# mdu29.net
KiCad netlist of a schematic drawn in EAGLE
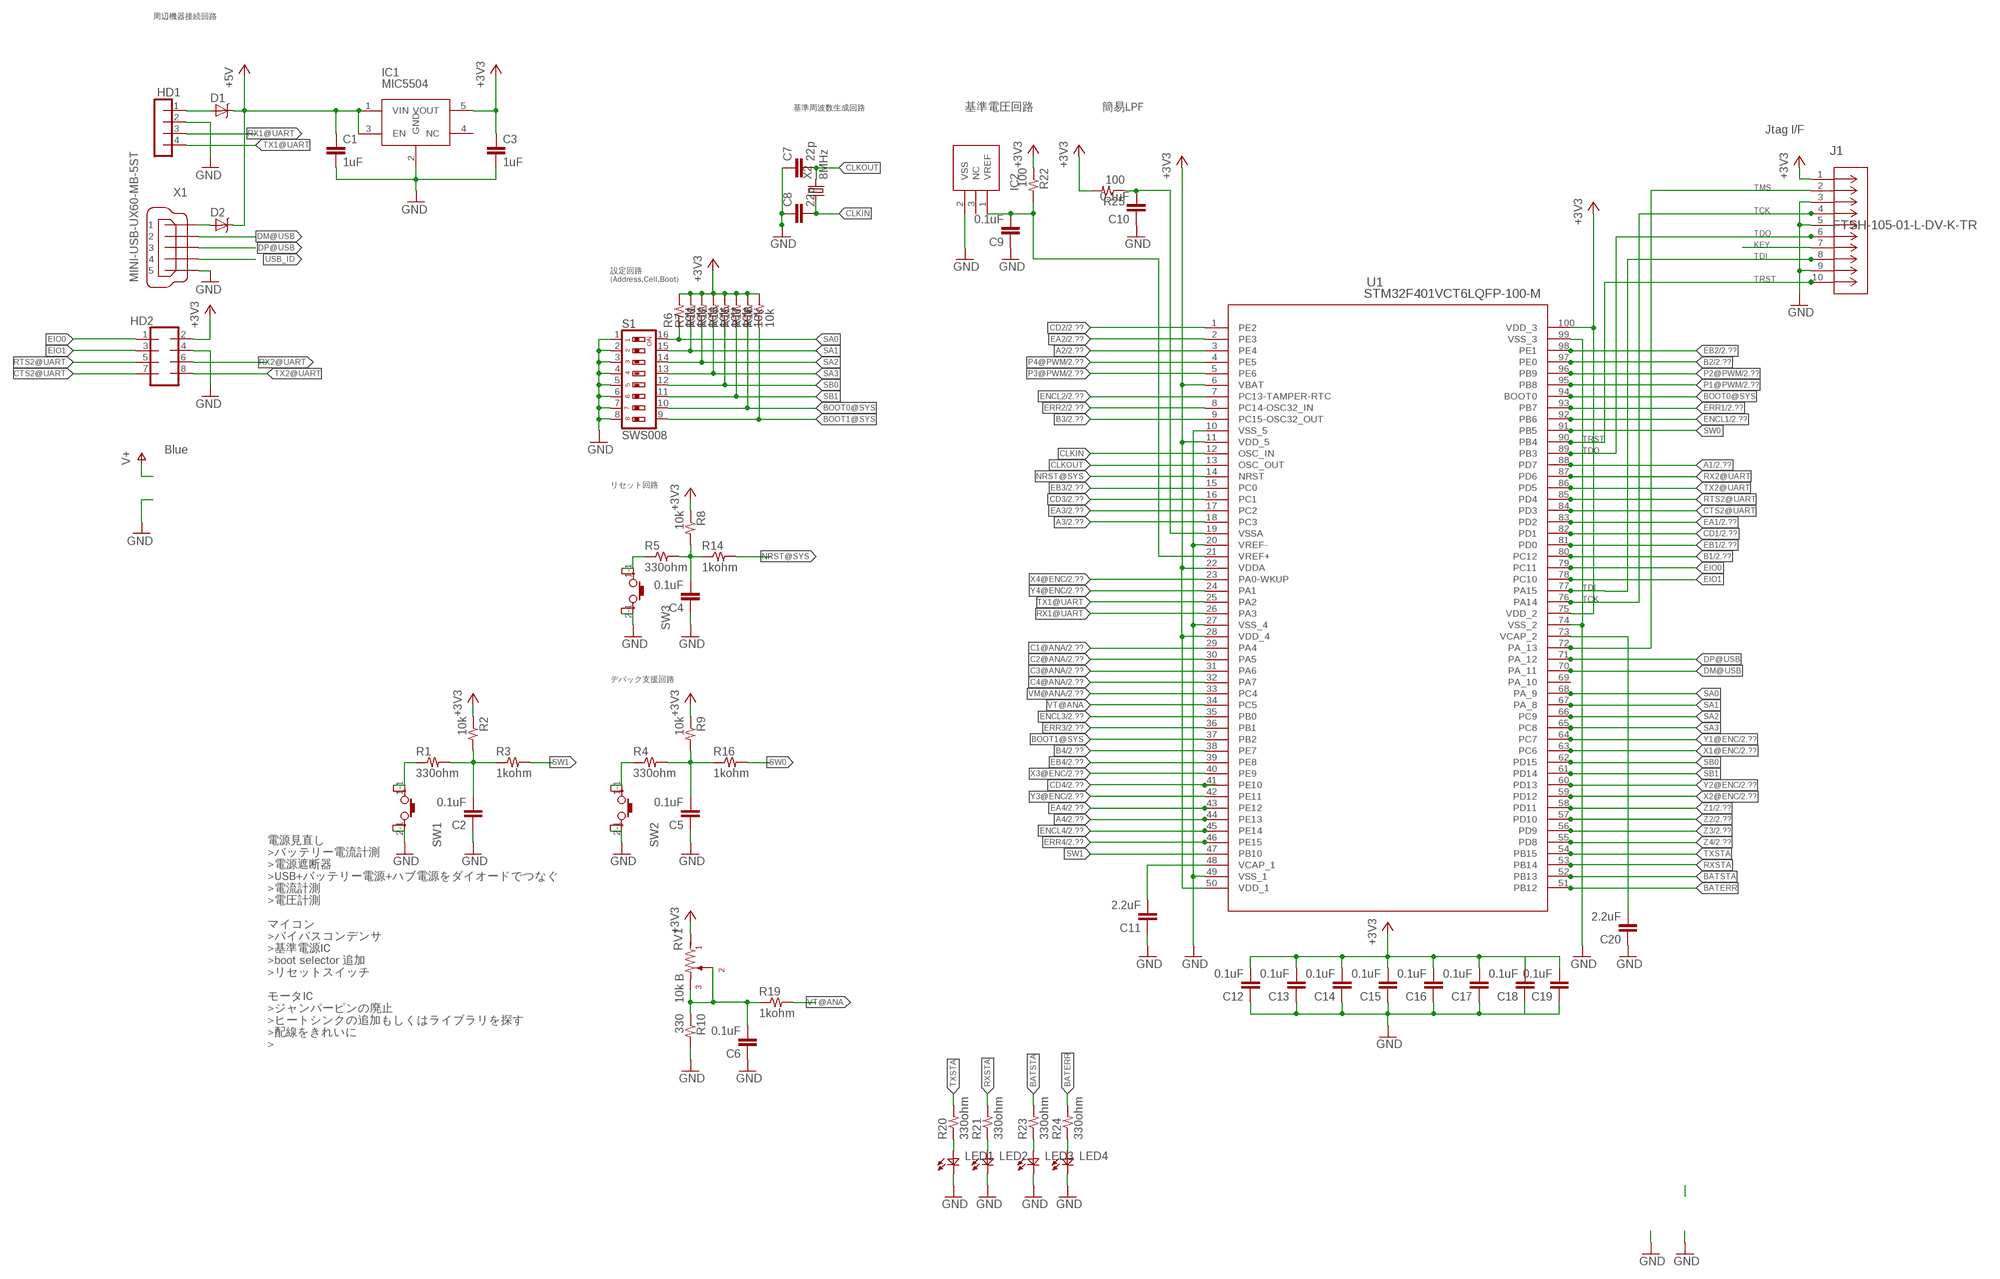
[diagram p0: schematic, sheet 1]
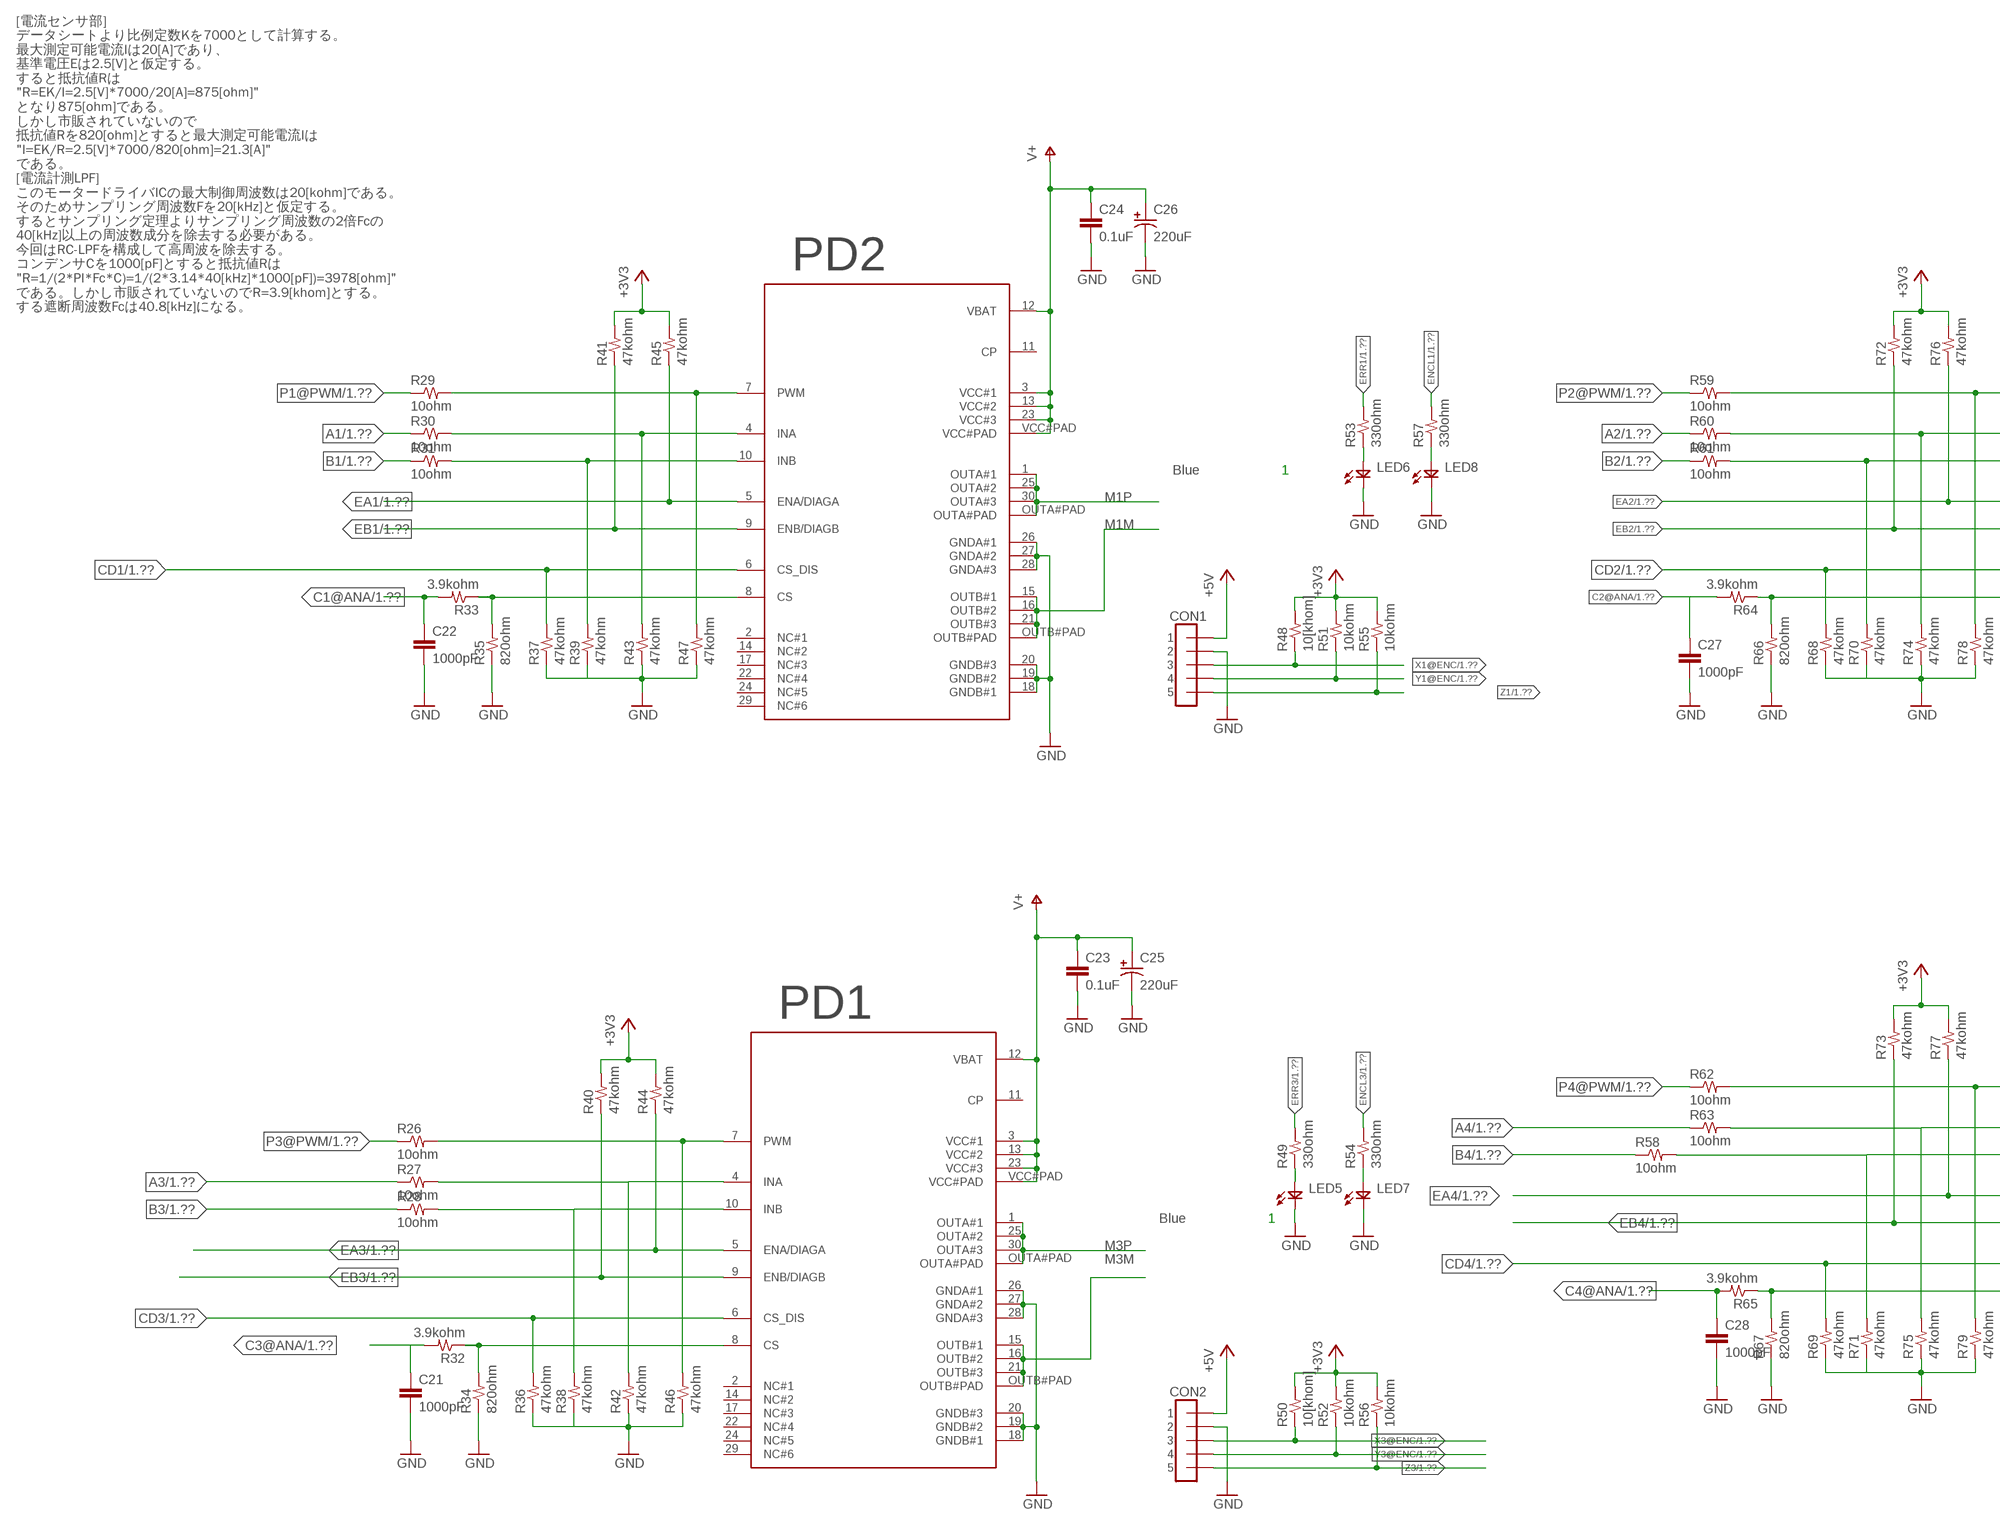
[diagram p1: schematic, sheet 2, part 1 of 2]
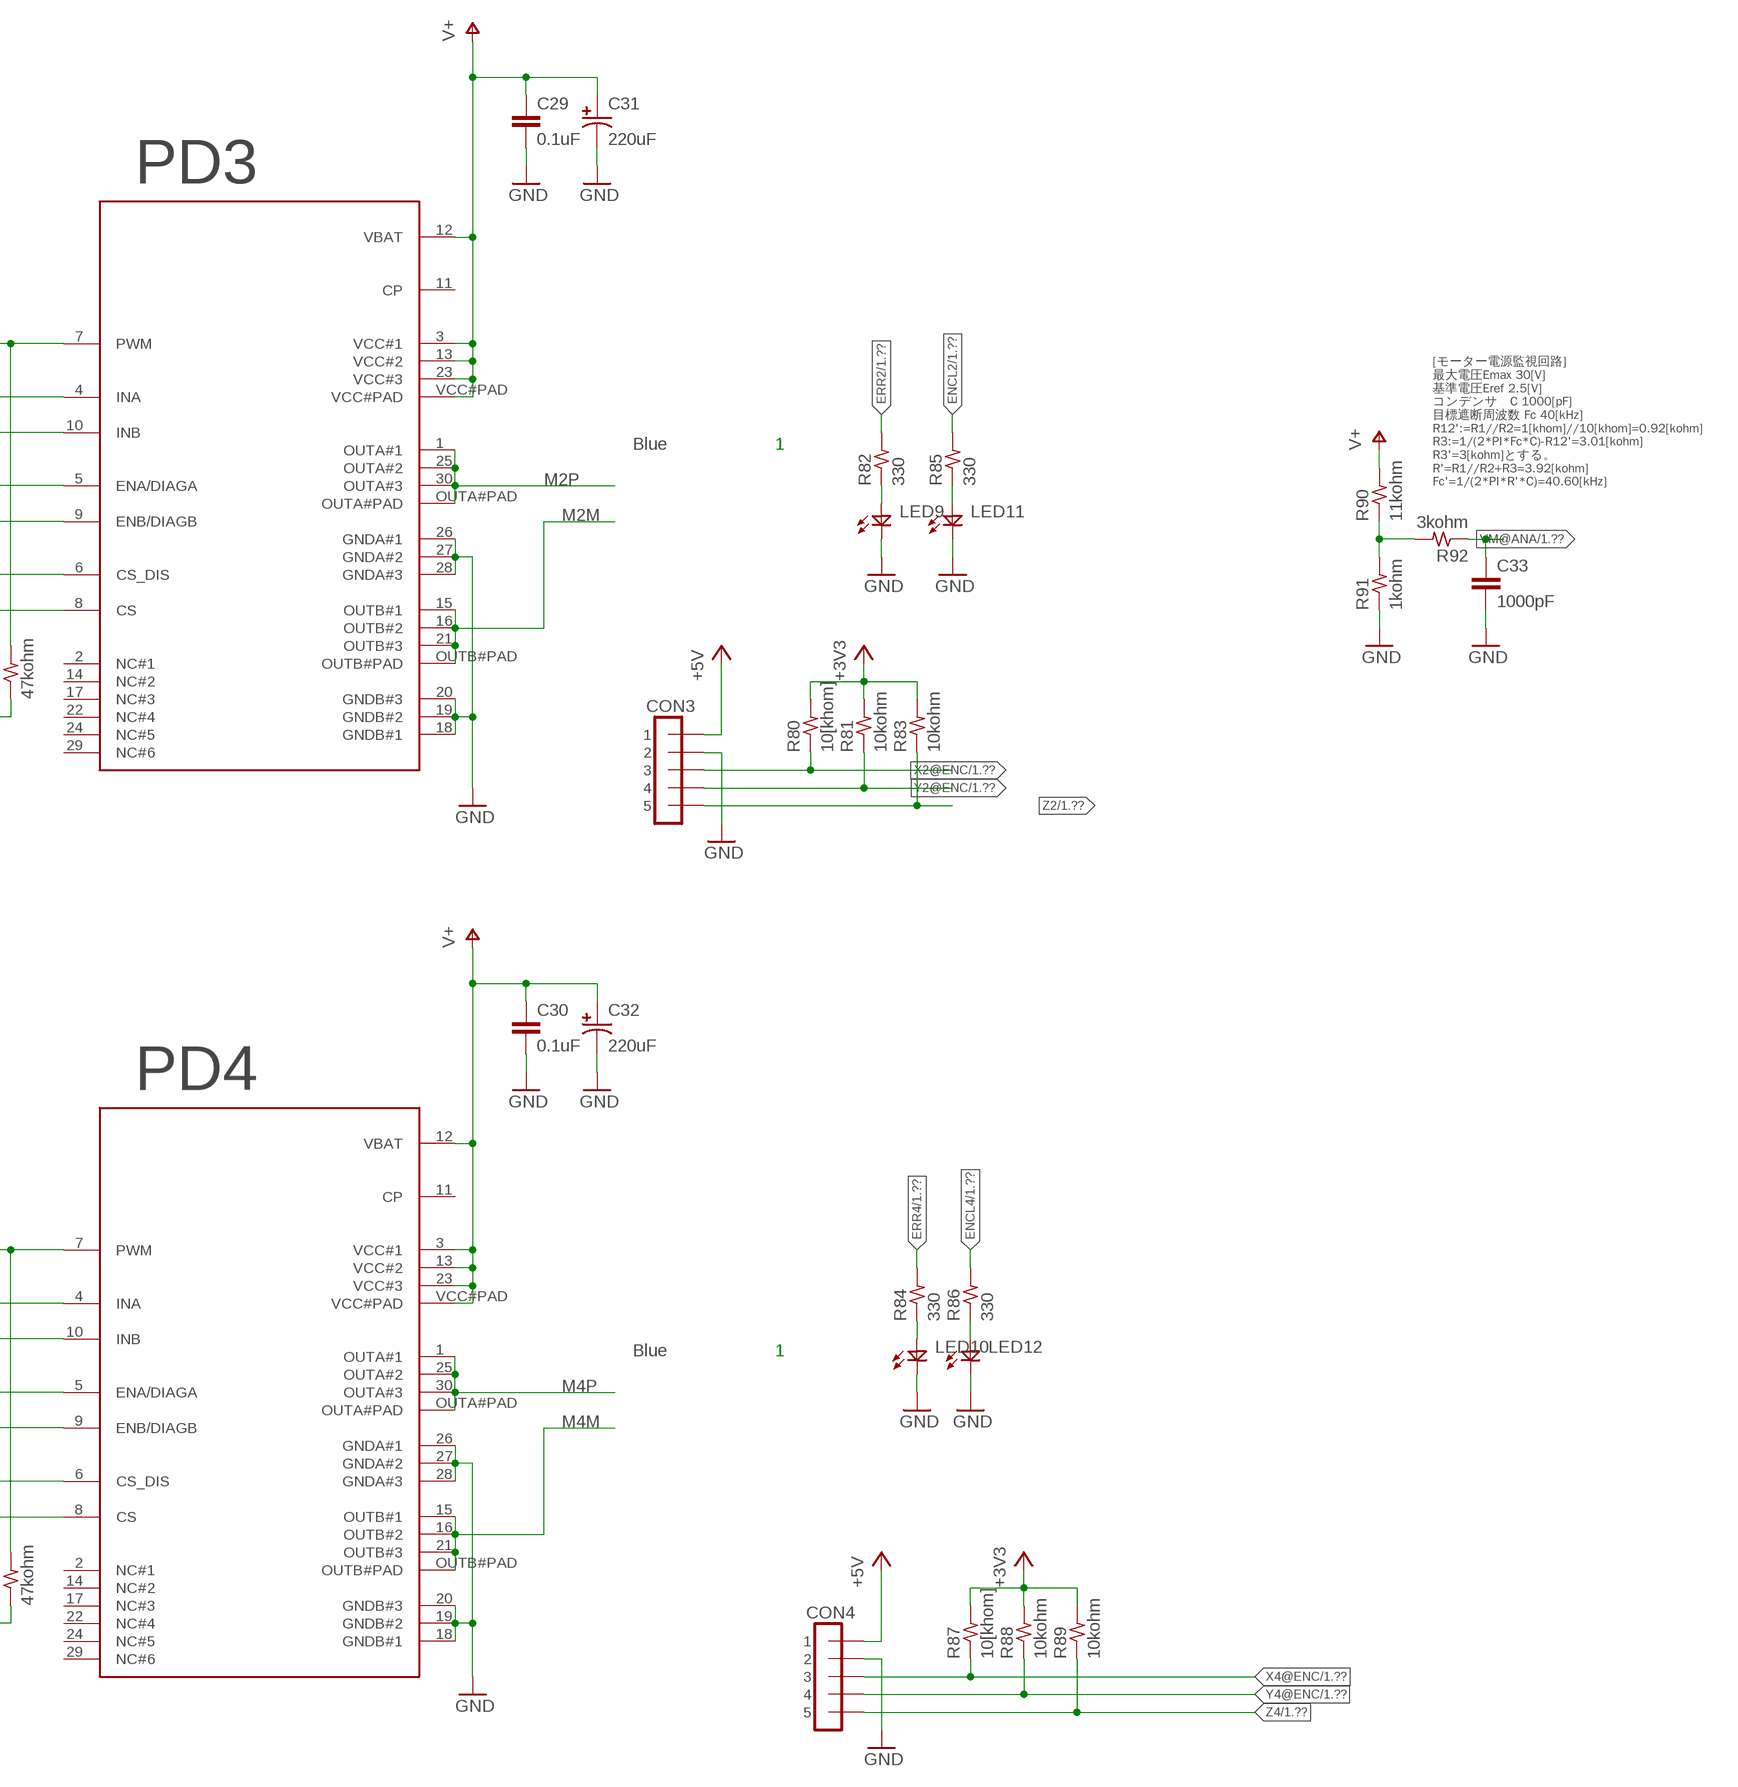
[diagram p2: schematic, sheet 2, part 2 of 2]

(export (version "E")
  (design (tool "Eeschema 10.0.6"))
  (components
    (comp (ref "C21")
      (value "1000pF")
      (footprint "eagle-import:1608")
      (libsource (lib "eagle-import") (part "C1608"))
    )
    (comp (ref "C22")
      (value "1000pF")
      (footprint "eagle-import:1608")
      (libsource (lib "eagle-import") (part "C1608"))
    )
    (comp (ref "C23")
      (value "0.1uF")
      (footprint "eagle-import:1608")
      (libsource (lib "eagle-import") (part "C1608"))
    )
    (comp (ref "C24")
      (value "0.1uF")
      (footprint "eagle-import:1608")
      (libsource (lib "eagle-import") (part "C1608"))
    )
    (comp (ref "C25")
      (value "220uF")
      (footprint "eagle-import:ES-12.5")
      (libsource (lib "eagle-import") (part "CPOLS-12.5"))
    )
    (comp (ref "C26")
      (value "220uF")
      (footprint "eagle-import:ES-12.5")
      (libsource (lib "eagle-import") (part "CPOLS-12.5"))
    )
    (comp (ref "C27")
      (value "1000pF")
      (footprint "eagle-import:1608")
      (libsource (lib "eagle-import") (part "C1608"))
    )
    (comp (ref "C28")
      (value "1000pF")
      (footprint "eagle-import:1608")
      (libsource (lib "eagle-import") (part "C1608"))
    )
    (comp (ref "C29")
      (value "0.1uF")
      (footprint "eagle-import:1608")
      (libsource (lib "eagle-import") (part "C1608"))
    )
    (comp (ref "C30")
      (value "0.1uF")
      (footprint "eagle-import:1608")
      (libsource (lib "eagle-import") (part "C1608"))
    )
    (comp (ref "C31")
      (value "220uF")
      (footprint "eagle-import:ES-12.5")
      (libsource (lib "eagle-import") (part "CPOLS-12.5"))
    )
    (comp (ref "C32")
      (value "220uF")
      (footprint "eagle-import:ES-12.5")
      (libsource (lib "eagle-import") (part "CPOLS-12.5"))
    )
    (comp (ref "C33")
      (value "1000pF")
      (footprint "eagle-import:1608")
      (libsource (lib "eagle-import") (part "C1608"))
    )
    (comp (ref "CON1")
      (value "CON-5")
      (footprint "eagle-import:5-L")
      (libsource (lib "eagle-import") (part "CON-5"))
    )
    (comp (ref "CON2")
      (value "CON-5")
      (footprint "eagle-import:5-L")
      (libsource (lib "eagle-import") (part "CON-5"))
    )
    (comp (ref "CON3")
      (value "CON-5")
      (footprint "eagle-import:5-L")
      (libsource (lib "eagle-import") (part "CON-5"))
    )
    (comp (ref "CON4")
      (value "CON-5")
      (footprint "eagle-import:5-L")
      (libsource (lib "eagle-import") (part "CON-5"))
    )
    (comp (ref "LED5")
      (value "LED1608")
      (footprint "eagle-import:1608")
      (libsource (lib "eagle-import") (part "LED1608"))
    )
    (comp (ref "LED6")
      (value "LED1608")
      (footprint "eagle-import:1608")
      (libsource (lib "eagle-import") (part "LED1608"))
    )
    (comp (ref "LED7")
      (value "LED1608")
      (footprint "eagle-import:1608")
      (libsource (lib "eagle-import") (part "LED1608"))
    )
    (comp (ref "LED8")
      (value "LED1608")
      (footprint "eagle-import:1608")
      (libsource (lib "eagle-import") (part "LED1608"))
    )
    (comp (ref "LED9")
      (value "LED1608")
      (footprint "eagle-import:1608")
      (libsource (lib "eagle-import") (part "LED1608"))
    )
    (comp (ref "LED10")
      (value "LED1608")
      (footprint "eagle-import:1608")
      (libsource (lib "eagle-import") (part "LED1608"))
    )
    (comp (ref "LED11")
      (value "LED1608")
      (footprint "eagle-import:1608")
      (libsource (lib "eagle-import") (part "LED1608"))
    )
    (comp (ref "LED12")
      (value "LED1608")
      (footprint "eagle-import:1608")
      (libsource (lib "eagle-import") (part "LED1608"))
    )
    (comp (ref "PD1")
      (value "VNH5019")
      (footprint "eagle-import:VNH5019")
      (libsource (lib "eagle-import") (part "VNH5019"))
    )
    (comp (ref "PD2")
      (value "VNH5019")
      (footprint "eagle-import:VNH5019")
      (libsource (lib "eagle-import") (part "VNH5019"))
    )
    (comp (ref "PD3")
      (value "VNH5019")
      (footprint "eagle-import:VNH5019")
      (libsource (lib "eagle-import") (part "VNH5019"))
    )
    (comp (ref "PD4")
      (value "VNH5019")
      (footprint "eagle-import:VNH5019")
      (libsource (lib "eagle-import") (part "VNH5019"))
    )
    (comp (ref "R26")
      (value "10ohm")
      (footprint "eagle-import:1608")
      (libsource (lib "eagle-import") (part "R1608"))
    )
    (comp (ref "R27")
      (value "10ohm")
      (footprint "eagle-import:1608")
      (libsource (lib "eagle-import") (part "R1608"))
    )
    (comp (ref "R28")
      (value "10ohm")
      (footprint "eagle-import:1608")
      (libsource (lib "eagle-import") (part "R1608"))
    )
    (comp (ref "R29")
      (value "10ohm")
      (footprint "eagle-import:1608")
      (libsource (lib "eagle-import") (part "R1608"))
    )
    (comp (ref "R30")
      (value "10ohm")
      (footprint "eagle-import:1608")
      (libsource (lib "eagle-import") (part "R1608"))
    )
    (comp (ref "R31")
      (value "10ohm")
      (footprint "eagle-import:1608")
      (libsource (lib "eagle-import") (part "R1608"))
    )
    (comp (ref "R32")
      (value "3.9kohm")
      (footprint "eagle-import:1608")
      (libsource (lib "eagle-import") (part "R1608"))
    )
    (comp (ref "R33")
      (value "3.9kohm")
      (footprint "eagle-import:1608")
      (libsource (lib "eagle-import") (part "R1608"))
    )
    (comp (ref "R34")
      (value "820ohm")
      (footprint "eagle-import:1608")
      (libsource (lib "eagle-import") (part "R1608"))
    )
    (comp (ref "R35")
      (value "820ohm")
      (footprint "eagle-import:1608")
      (libsource (lib "eagle-import") (part "R1608"))
    )
    (comp (ref "R36")
      (value "47kohm")
      (footprint "eagle-import:1608")
      (libsource (lib "eagle-import") (part "R1608"))
    )
    (comp (ref "R37")
      (value "47kohm")
      (footprint "eagle-import:1608")
      (libsource (lib "eagle-import") (part "R1608"))
    )
    (comp (ref "R38")
      (value "47kohm")
      (footprint "eagle-import:1608")
      (libsource (lib "eagle-import") (part "R1608"))
    )
    (comp (ref "R39")
      (value "47kohm")
      (footprint "eagle-import:1608")
      (libsource (lib "eagle-import") (part "R1608"))
    )
    (comp (ref "R40")
      (value "47kohm")
      (footprint "eagle-import:1608")
      (libsource (lib "eagle-import") (part "R1608"))
    )
    (comp (ref "R41")
      (value "47kohm")
      (footprint "eagle-import:1608")
      (libsource (lib "eagle-import") (part "R1608"))
    )
    (comp (ref "R42")
      (value "47kohm")
      (footprint "eagle-import:1608")
      (libsource (lib "eagle-import") (part "R1608"))
    )
    (comp (ref "R43")
      (value "47kohm")
      (footprint "eagle-import:1608")
      (libsource (lib "eagle-import") (part "R1608"))
    )
    (comp (ref "R44")
      (value "47kohm")
      (footprint "eagle-import:1608")
      (libsource (lib "eagle-import") (part "R1608"))
    )
    (comp (ref "R45")
      (value "47kohm")
      (footprint "eagle-import:1608")
      (libsource (lib "eagle-import") (part "R1608"))
    )
    (comp (ref "R46")
      (value "47kohm")
      (footprint "eagle-import:1608")
      (libsource (lib "eagle-import") (part "R1608"))
    )
    (comp (ref "R47")
      (value "47kohm")
      (footprint "eagle-import:1608")
      (libsource (lib "eagle-import") (part "R1608"))
    )
    (comp (ref "R48")
      (value "10[khom]")
      (footprint "eagle-import:1608")
      (libsource (lib "eagle-import") (part "R1608"))
    )
    (comp (ref "R49")
      (value "330ohm")
      (footprint "eagle-import:1608")
      (libsource (lib "eagle-import") (part "R1608"))
    )
    (comp (ref "R50")
      (value "10[khom]")
      (footprint "eagle-import:1608")
      (libsource (lib "eagle-import") (part "R1608"))
    )
    (comp (ref "R51")
      (value "10kohm")
      (footprint "eagle-import:1608")
      (libsource (lib "eagle-import") (part "R1608"))
    )
    (comp (ref "R52")
      (value "10kohm")
      (footprint "eagle-import:1608")
      (libsource (lib "eagle-import") (part "R1608"))
    )
    (comp (ref "R53")
      (value "330ohm")
      (footprint "eagle-import:1608")
      (libsource (lib "eagle-import") (part "R1608"))
    )
    (comp (ref "R54")
      (value "330ohm")
      (footprint "eagle-import:1608")
      (libsource (lib "eagle-import") (part "R1608"))
    )
    (comp (ref "R55")
      (value "10kohm")
      (footprint "eagle-import:1608")
      (libsource (lib "eagle-import") (part "R1608"))
    )
    (comp (ref "R56")
      (value "10kohm")
      (footprint "eagle-import:1608")
      (libsource (lib "eagle-import") (part "R1608"))
    )
    (comp (ref "R57")
      (value "330ohm")
      (footprint "eagle-import:1608")
      (libsource (lib "eagle-import") (part "R1608"))
    )
    (comp (ref "R58")
      (value "10ohm")
      (footprint "eagle-import:1608")
      (libsource (lib "eagle-import") (part "R1608"))
    )
    (comp (ref "R59")
      (value "10ohm")
      (footprint "eagle-import:1608")
      (libsource (lib "eagle-import") (part "R1608"))
    )
    (comp (ref "R60")
      (value "10ohm")
      (footprint "eagle-import:1608")
      (libsource (lib "eagle-import") (part "R1608"))
    )
    (comp (ref "R61")
      (value "10ohm")
      (footprint "eagle-import:1608")
      (libsource (lib "eagle-import") (part "R1608"))
    )
    (comp (ref "R62")
      (value "10ohm")
      (footprint "eagle-import:1608")
      (libsource (lib "eagle-import") (part "R1608"))
    )
    (comp (ref "R63")
      (value "10ohm")
      (footprint "eagle-import:1608")
      (libsource (lib "eagle-import") (part "R1608"))
    )
    (comp (ref "R64")
      (value "3.9kohm")
      (footprint "eagle-import:1608")
      (libsource (lib "eagle-import") (part "R1608"))
    )
    (comp (ref "R65")
      (value "3.9kohm")
      (footprint "eagle-import:1608")
      (libsource (lib "eagle-import") (part "R1608"))
    )
    (comp (ref "R66")
      (value "820ohm")
      (footprint "eagle-import:1608")
      (libsource (lib "eagle-import") (part "R1608"))
    )
    (comp (ref "R67")
      (value "820ohm")
      (footprint "eagle-import:1608")
      (libsource (lib "eagle-import") (part "R1608"))
    )
    (comp (ref "R68")
      (value "47kohm")
      (footprint "eagle-import:1608")
      (libsource (lib "eagle-import") (part "R1608"))
    )
    (comp (ref "R69")
      (value "47kohm")
      (footprint "eagle-import:1608")
      (libsource (lib "eagle-import") (part "R1608"))
    )
    (comp (ref "R70")
      (value "47kohm")
      (footprint "eagle-import:1608")
      (libsource (lib "eagle-import") (part "R1608"))
    )
    (comp (ref "R71")
      (value "47kohm")
      (footprint "eagle-import:1608")
      (libsource (lib "eagle-import") (part "R1608"))
    )
    (comp (ref "R72")
      (value "47kohm")
      (footprint "eagle-import:1608")
      (libsource (lib "eagle-import") (part "R1608"))
    )
    (comp (ref "R73")
      (value "47kohm")
      (footprint "eagle-import:1608")
      (libsource (lib "eagle-import") (part "R1608"))
    )
    (comp (ref "R74")
      (value "47kohm")
      (footprint "eagle-import:1608")
      (libsource (lib "eagle-import") (part "R1608"))
    )
    (comp (ref "R75")
      (value "47kohm")
      (footprint "eagle-import:1608")
      (libsource (lib "eagle-import") (part "R1608"))
    )
    (comp (ref "R76")
      (value "47kohm")
      (footprint "eagle-import:1608")
      (libsource (lib "eagle-import") (part "R1608"))
    )
    (comp (ref "R77")
      (value "47kohm")
      (footprint "eagle-import:1608")
      (libsource (lib "eagle-import") (part "R1608"))
    )
    (comp (ref "R78")
      (value "47kohm")
      (footprint "eagle-import:1608")
      (libsource (lib "eagle-import") (part "R1608"))
    )
    (comp (ref "R79")
      (value "47kohm")
      (footprint "eagle-import:1608")
      (libsource (lib "eagle-import") (part "R1608"))
    )
    (comp (ref "R80")
      (value "10[khom]")
      (footprint "eagle-import:1608")
      (libsource (lib "eagle-import") (part "R1608"))
    )
    (comp (ref "R81")
      (value "10kohm")
      (footprint "eagle-import:1608")
      (libsource (lib "eagle-import") (part "R1608"))
    )
    (comp (ref "R82")
      (value "330")
      (footprint "eagle-import:1608")
      (libsource (lib "eagle-import") (part "R1608"))
    )
    (comp (ref "R83")
      (value "10kohm")
      (footprint "eagle-import:1608")
      (libsource (lib "eagle-import") (part "R1608"))
    )
    (comp (ref "R84")
      (value "330")
      (footprint "eagle-import:1608")
      (libsource (lib "eagle-import") (part "R1608"))
    )
    (comp (ref "R85")
      (value "330")
      (footprint "eagle-import:1608")
      (libsource (lib "eagle-import") (part "R1608"))
    )
    (comp (ref "R86")
      (value "330")
      (footprint "eagle-import:1608")
      (libsource (lib "eagle-import") (part "R1608"))
    )
    (comp (ref "R87")
      (value "10[khom]")
      (footprint "eagle-import:1608")
      (libsource (lib "eagle-import") (part "R1608"))
    )
    (comp (ref "R88")
      (value "10kohm")
      (footprint "eagle-import:1608")
      (libsource (lib "eagle-import") (part "R1608"))
    )
    (comp (ref "R89")
      (value "10kohm")
      (footprint "eagle-import:1608")
      (libsource (lib "eagle-import") (part "R1608"))
    )
    (comp (ref "R90")
      (value "11kohm")
      (footprint "eagle-import:1608")
      (libsource (lib "eagle-import") (part "R1608"))
    )
    (comp (ref "R91")
      (value "1kohm")
      (footprint "eagle-import:1608")
      (libsource (lib "eagle-import") (part "R1608"))
    )
    (comp (ref "R92")
      (value "3kohm")
      (footprint "eagle-import:1608")
      (libsource (lib "eagle-import") (part "R1608"))
    )
    (comp (ref "C1")
      (value "1uF")
      (footprint "eagle-import:1608")
      (libsource (lib "eagle-import") (part "C1608"))
    )
    (comp (ref "C2")
      (value "0.1uF")
      (footprint "eagle-import:1608")
      (libsource (lib "eagle-import") (part "C1608"))
    )
    (comp (ref "C3")
      (value "1uF")
      (footprint "eagle-import:1608")
      (libsource (lib "eagle-import") (part "C1608"))
    )
    (comp (ref "C4")
      (value "0.1uF")
      (footprint "eagle-import:1608")
      (libsource (lib "eagle-import") (part "C1608"))
    )
    (comp (ref "C5")
      (value "0.1uF")
      (footprint "eagle-import:1608")
      (libsource (lib "eagle-import") (part "C1608"))
    )
    (comp (ref "C6")
      (value "0.1uF")
      (footprint "eagle-import:1608")
      (libsource (lib "eagle-import") (part "C1608"))
    )
    (comp (ref "C7")
      (value "22p")
      (footprint "eagle-import:1608")
      (libsource (lib "eagle-import") (part "C1608"))
    )
    (comp (ref "C8")
      (value "22p")
      (footprint "eagle-import:1608")
      (libsource (lib "eagle-import") (part "C1608"))
    )
    (comp (ref "C9")
      (value "0.1uF")
      (footprint "eagle-import:1608")
      (libsource (lib "eagle-import") (part "C1608"))
    )
    (comp (ref "C10")
      (value "0.1uF")
      (footprint "eagle-import:1608")
      (libsource (lib "eagle-import") (part "C1608"))
    )
    (comp (ref "C11")
      (value "2.2uF")
      (footprint "eagle-import:1608")
      (libsource (lib "eagle-import") (part "C1608"))
    )
    (comp (ref "C12")
      (value "0.1uF")
      (footprint "eagle-import:1608")
      (libsource (lib "eagle-import") (part "C1608"))
    )
    (comp (ref "C13")
      (value "0.1uF")
      (footprint "eagle-import:1608")
      (libsource (lib "eagle-import") (part "C1608"))
    )
    (comp (ref "C14")
      (value "0.1uF")
      (footprint "eagle-import:1608")
      (libsource (lib "eagle-import") (part "C1608"))
    )
    (comp (ref "C15")
      (value "0.1uF")
      (footprint "eagle-import:1608")
      (libsource (lib "eagle-import") (part "C1608"))
    )
    (comp (ref "C16")
      (value "0.1uF")
      (footprint "eagle-import:1608")
      (libsource (lib "eagle-import") (part "C1608"))
    )
    (comp (ref "C17")
      (value "0.1uF")
      (footprint "eagle-import:1608")
      (libsource (lib "eagle-import") (part "C1608"))
    )
    (comp (ref "C18")
      (value "0.1uF")
      (footprint "eagle-import:1608")
      (libsource (lib "eagle-import") (part "C1608"))
    )
    (comp (ref "C19")
      (value "0.1uF")
      (footprint "eagle-import:1608")
      (libsource (lib "eagle-import") (part "C1608"))
    )
    (comp (ref "C20")
      (value "2.2uF")
      (footprint "eagle-import:1608")
      (libsource (lib "eagle-import") (part "C1608"))
    )
    (comp (ref "D1")
      (value "ZENER-SOD523")
      (footprint "eagle-import:SOD523")
      (libsource (lib "eagle-import") (part "ZENER-SOD523"))
    )
    (comp (ref "D2")
      (value "ZENER-SOD523")
      (footprint "eagle-import:SOD523")
      (libsource (lib "eagle-import") (part "ZENER-SOD523"))
    )
    (comp (ref "HD1")
      (value "1X4L")
      (footprint "eagle-import:1X4-L")
      (libsource (lib "eagle-import") (part "1X4L"))
    )
    (comp (ref "HD2")
      (value "2X4I")
      (footprint "eagle-import:2X4-I")
      (libsource (lib "eagle-import") (part "2X4I"))
    )
    (comp (ref "IC1")
      (value "MIC5504")
      (footprint "eagle-import:SOT95P270X145-5N")
      (libsource (lib "eagle-import") (part "MIC5504"))
    )
    (comp (ref "IC2")
      (value "LM4040")
      (footprint "eagle-import:SOT23")
      (libsource (lib "eagle-import") (part "LM4040"))
    )
    (comp (ref "J1")
      (value "FTSH-105-01-L-DV-K-TR")
      (footprint "eagle-import:CON10_2X5_DUK_FTSH")
      (fields
        (field (name "DIGIKEYPARTNUMBER") "FTSH-105-01-L-DV-K-TR-ND")
        (field (name "COPYRIGHT") "Copyright (C) 2015 Accelerated Designs. All rights reserved")
      )
      (libsource (lib "eagle-import") (part "FTSH-105-01-L-DV-K-TR"))
    )
    (comp (ref "LED1")
      (value "LED1608")
      (footprint "eagle-import:1608")
      (libsource (lib "eagle-import") (part "LED1608"))
    )
    (comp (ref "LED2")
      (value "LED1608")
      (footprint "eagle-import:1608")
      (libsource (lib "eagle-import") (part "LED1608"))
    )
    (comp (ref "LED3")
      (value "LED1608")
      (footprint "eagle-import:1608")
      (libsource (lib "eagle-import") (part "LED1608"))
    )
    (comp (ref "LED4")
      (value "LED1608")
      (footprint "eagle-import:1608")
      (libsource (lib "eagle-import") (part "LED1608"))
    )
    (comp (ref "R1")
      (value "330ohm")
      (footprint "eagle-import:1608")
      (libsource (lib "eagle-import") (part "R1608"))
    )
    (comp (ref "R2")
      (value "10k")
      (footprint "eagle-import:1608")
      (libsource (lib "eagle-import") (part "R1608"))
    )
    (comp (ref "R3")
      (value "1kohm")
      (footprint "eagle-import:1608")
      (libsource (lib "eagle-import") (part "R1608"))
    )
    (comp (ref "R4")
      (value "330ohm")
      (footprint "eagle-import:1608")
      (libsource (lib "eagle-import") (part "R1608"))
    )
    (comp (ref "R5")
      (value "330ohm")
      (footprint "eagle-import:1608")
      (libsource (lib "eagle-import") (part "R1608"))
    )
    (comp (ref "R6")
      (value "10k")
      (footprint "eagle-import:1608")
      (libsource (lib "eagle-import") (part "R1608"))
    )
    (comp (ref "R7")
      (value "10k")
      (footprint "eagle-import:1608")
      (libsource (lib "eagle-import") (part "R1608"))
    )
    (comp (ref "R8")
      (value "10k")
      (footprint "eagle-import:1608")
      (libsource (lib "eagle-import") (part "R1608"))
    )
    (comp (ref "R9")
      (value "10k")
      (footprint "eagle-import:1608")
      (libsource (lib "eagle-import") (part "R1608"))
    )
    (comp (ref "R10")
      (value "330")
      (footprint "eagle-import:1608")
      (libsource (lib "eagle-import") (part "R1608"))
    )
    (comp (ref "R11")
      (value "10k")
      (footprint "eagle-import:1608")
      (libsource (lib "eagle-import") (part "R1608"))
    )
    (comp (ref "R12")
      (value "10k")
      (footprint "eagle-import:1608")
      (libsource (lib "eagle-import") (part "R1608"))
    )
    (comp (ref "R13")
      (value "10k")
      (footprint "eagle-import:1608")
      (libsource (lib "eagle-import") (part "R1608"))
    )
    (comp (ref "R14")
      (value "1kohm")
      (footprint "eagle-import:1608")
      (libsource (lib "eagle-import") (part "R1608"))
    )
    (comp (ref "R15")
      (value "10k")
      (footprint "eagle-import:1608")
      (libsource (lib "eagle-import") (part "R1608"))
    )
    (comp (ref "R16")
      (value "1kohm")
      (footprint "eagle-import:1608")
      (libsource (lib "eagle-import") (part "R1608"))
    )
    (comp (ref "R17")
      (value "10k")
      (footprint "eagle-import:1608")
      (libsource (lib "eagle-import") (part "R1608"))
    )
    (comp (ref "R18")
      (value "10k")
      (footprint "eagle-import:1608")
      (libsource (lib "eagle-import") (part "R1608"))
    )
    (comp (ref "R19")
      (value "1kohm")
      (footprint "eagle-import:1608")
      (libsource (lib "eagle-import") (part "R1608"))
    )
    (comp (ref "R20")
      (value "330ohm")
      (footprint "eagle-import:1608")
      (libsource (lib "eagle-import") (part "R1608"))
    )
    (comp (ref "R21")
      (value "330ohm")
      (footprint "eagle-import:1608")
      (libsource (lib "eagle-import") (part "R1608"))
    )
    (comp (ref "R22")
      (value "100")
      (footprint "eagle-import:1608")
      (libsource (lib "eagle-import") (part "R1608"))
    )
    (comp (ref "R23")
      (value "330ohm")
      (footprint "eagle-import:1608")
      (libsource (lib "eagle-import") (part "R1608"))
    )
    (comp (ref "R24")
      (value "330ohm")
      (footprint "eagle-import:1608")
      (libsource (lib "eagle-import") (part "R1608"))
    )
    (comp (ref "R25")
      (value "100")
      (footprint "eagle-import:1608")
      (libsource (lib "eagle-import") (part "R1608"))
    )
    (comp (ref "RV1")
      (value "10k B")
      (footprint "eagle-import:RV")
      (libsource (lib "eagle-import") (part "RV"))
    )
    (comp (ref "S1")
      (value "SWS008")
      (footprint "eagle-import:SMS-008")
      (libsource (lib "eagle-import") (part "SWS008"))
    )
    (comp (ref "SW1")
      (value "TACTSW1")
      (footprint "eagle-import:PUSHSW-1")
      (libsource (lib "eagle-import") (part "TACTSW1"))
    )
    (comp (ref "SW2")
      (value "TACTSW1")
      (footprint "eagle-import:PUSHSW-1")
      (libsource (lib "eagle-import") (part "TACTSW1"))
    )
    (comp (ref "SW3")
      (value "TACTSW1")
      (footprint "eagle-import:PUSHSW-1")
      (libsource (lib "eagle-import") (part "TACTSW1"))
    )
    (comp (ref "U1")
      (value "STM32F401VCT6LQFP-100-M")
      (footprint "eagle-import:LQFP-100-M")
      (fields (field (name "MANUFACTURER_PART_NUMBER") "STM32F401VCT6"))
      (libsource (lib "eagle-import") (part "STM32F401VCT6LQFP-100-M"))
    )
    (comp (ref "X1")
      (value "MINI-USB-UX60-MB-5ST")
      (footprint "eagle-import:UX60-MB-5ST")
      (libsource (lib "eagle-import") (part "MINI-USB-UX60-MB-5ST"))
    )
    (comp (ref "X2")
      (value "8MHz")
      (footprint "eagle-import:XTAL")
      (libsource (lib "eagle-import") (part "CRYSTALHC49S"))
    )
  )
  (nets
    (net (code "1") (name "+3V3") (class "Default")
      (node (ref "C12") (pin "2") (pinfunction "2_2") (pintype "passive"))
      (node (ref "C13") (pin "2") (pinfunction "2_2") (pintype "passive"))
      (node (ref "C14") (pin "2") (pinfunction "2_2") (pintype "passive"))
      (node (ref "C15") (pin "2") (pinfunction "2_2") (pintype "passive"))
      (node (ref "C16") (pin "2") (pinfunction "2_2") (pintype "passive"))
      (node (ref "C17") (pin "2") (pinfunction "2_2") (pintype "passive"))
      (node (ref "C18") (pin "2") (pinfunction "2_2") (pintype "passive"))
      (node (ref "C19") (pin "2") (pinfunction "2_2") (pintype "passive"))
      (node (ref "C3") (pin "1") (pinfunction "1_1") (pintype "passive"))
      (node (ref "HD2") (pin "2") (pinfunction "2_2") (pintype "passive"))
      (node (ref "IC1") (pin "5") (pinfunction "VOUT_5") (pintype "power_in"))
      (node (ref "J1") (pin "1") (pinfunction "1_1") (pintype "passive"))
      (node (ref "R11") (pin "2") (pinfunction "2_2") (pintype "passive"))
      (node (ref "R12") (pin "2") (pinfunction "2_2") (pintype "passive"))
      (node (ref "R13") (pin "2") (pinfunction "2_2") (pintype "passive"))
      (node (ref "R15") (pin "2") (pinfunction "2_2") (pintype "passive"))
      (node (ref "R17") (pin "2") (pinfunction "2_2") (pintype "passive"))
      (node (ref "R18") (pin "2") (pinfunction "2_2") (pintype "passive"))
      (node (ref "R2") (pin "1") (pinfunction "1_1") (pintype "passive"))
      (node (ref "R22") (pin "1") (pinfunction "1_1") (pintype "passive"))
      (node (ref "R25") (pin "2") (pinfunction "2_2") (pintype "passive"))
      (node (ref "R40") (pin "2") (pinfunction "2_2") (pintype "passive"))
      (node (ref "R41") (pin "2") (pinfunction "2_2") (pintype "passive"))
      (node (ref "R44") (pin "2") (pinfunction "2_2") (pintype "passive"))
      (node (ref "R45") (pin "2") (pinfunction "2_2") (pintype "passive"))
      (node (ref "R48") (pin "2") (pinfunction "2_2") (pintype "passive"))
      (node (ref "R50") (pin "2") (pinfunction "2_2") (pintype "passive"))
      (node (ref "R51") (pin "2") (pinfunction "2_2") (pintype "passive"))
      (node (ref "R52") (pin "2") (pinfunction "2_2") (pintype "passive"))
      (node (ref "R55") (pin "2") (pinfunction "2_2") (pintype "passive"))
      (node (ref "R56") (pin "2") (pinfunction "2_2") (pintype "passive"))
      (node (ref "R6") (pin "2") (pinfunction "2_2") (pintype "passive"))
      (node (ref "R7") (pin "2") (pinfunction "2_2") (pintype "passive"))
      (node (ref "R72") (pin "2") (pinfunction "2_2") (pintype "passive"))
      (node (ref "R73") (pin "2") (pinfunction "2_2") (pintype "passive"))
      (node (ref "R76") (pin "2") (pinfunction "2_2") (pintype "passive"))
      (node (ref "R77") (pin "2") (pinfunction "2_2") (pintype "passive"))
      (node (ref "R8") (pin "1") (pinfunction "1_1") (pintype "passive"))
      (node (ref "R80") (pin "2") (pinfunction "2_2") (pintype "passive"))
      (node (ref "R81") (pin "2") (pinfunction "2_2") (pintype "passive"))
      (node (ref "R83") (pin "2") (pinfunction "2_2") (pintype "passive"))
      (node (ref "R87") (pin "2") (pinfunction "2_2") (pintype "passive"))
      (node (ref "R88") (pin "2") (pinfunction "2_2") (pintype "passive"))
      (node (ref "R89") (pin "2") (pinfunction "2_2") (pintype "passive"))
      (node (ref "R9") (pin "1") (pinfunction "1_1") (pintype "passive"))
      (node (ref "RV1") (pin "1") (pinfunction "1_1") (pintype "passive"))
      (node (ref "U1") (pin "100") (pinfunction "VDD_3_100") (pintype "power_in"))
      (node (ref "U1") (pin "11") (pinfunction "VDD_5_11") (pintype "power_in"))
      (node (ref "U1") (pin "22") (pinfunction "VDDA_22") (pintype "power_in"))
      (node (ref "U1") (pin "28") (pinfunction "VDD_4_28") (pintype "power_in"))
      (node (ref "U1") (pin "50") (pinfunction "VDD_1_50") (pintype "power_in"))
      (node (ref "U1") (pin "6") (pinfunction "VBAT_6") (pintype "power_in"))
      (node (ref "U1") (pin "75") (pinfunction "VDD_2_75") (pintype "power_in"))
    )
    (net (code "2") (name "+5V") (class "Default")
      (node (ref "C1") (pin "1") (pinfunction "1_1") (pintype "passive"))
      (node (ref "CON1") (pin "P$1") (pinfunction "1_P$1") (pintype "passive"))
      (node (ref "CON2") (pin "P$1") (pinfunction "1_P$1") (pintype "passive"))
      (node (ref "CON3") (pin "P$1") (pinfunction "1_P$1") (pintype "passive"))
      (node (ref "CON4") (pin "P$1") (pinfunction "1_P$1") (pintype "passive"))
      (node (ref "D1") (pin "K") (pinfunction "K_K") (pintype "passive"))
      (node (ref "D2") (pin "K") (pinfunction "K_K") (pintype "passive"))
      (node (ref "IC1") (pin "1") (pinfunction "VIN_1") (pintype "power_in"))
      (node (ref "IC1") (pin "3") (pinfunction "EN_3") (pintype "input"))
    )
    (net (code "3") (name "A1") (class "Default")
      (node (ref "R30") (pin "1") (pinfunction "1_1") (pintype "passive"))
      (node (ref "U1") (pin "88") (pinfunction "PD7_88") (pintype "bidirectional"))
    )
    (net (code "4") (name "A2") (class "Default")
      (node (ref "R60") (pin "1") (pinfunction "1_1") (pintype "passive"))
      (node (ref "U1") (pin "3") (pinfunction "PE4_3") (pintype "bidirectional"))
    )
    (net (code "5") (name "A3") (class "Default")
      (node (ref "R27") (pin "1") (pinfunction "1_1") (pintype "passive"))
      (node (ref "U1") (pin "18") (pinfunction "PC3_18") (pintype "bidirectional"))
    )
    (net (code "6") (name "A4") (class "Default")
      (node (ref "R63") (pin "1") (pinfunction "1_1") (pintype "passive"))
      (node (ref "U1") (pin "44") (pinfunction "PE13_44") (pintype "bidirectional"))
    )
    (net (code "7") (name "B1") (class "Default")
      (node (ref "R31") (pin "1") (pinfunction "1_1") (pintype "passive"))
      (node (ref "U1") (pin "80") (pinfunction "PC12_80") (pintype "bidirectional"))
    )
    (net (code "8") (name "B2") (class "Default")
      (node (ref "R61") (pin "1") (pinfunction "1_1") (pintype "passive"))
      (node (ref "U1") (pin "97") (pinfunction "PE0_97") (pintype "bidirectional"))
    )
    (net (code "9") (name "B3") (class "Default")
      (node (ref "R28") (pin "1") (pinfunction "1_1") (pintype "passive"))
      (node (ref "U1") (pin "9") (pinfunction "PC15-OSC32_OUT_9") (pintype "bidirectional"))
    )
    (net (code "10") (name "B4") (class "Default")
      (node (ref "R58") (pin "1") (pinfunction "1_1") (pintype "passive"))
      (node (ref "U1") (pin "38") (pinfunction "PE7_38") (pintype "bidirectional"))
    )
    (net (code "11") (name "BATERR") (class "Default")
      (node (ref "R24") (pin "2") (pinfunction "2_2") (pintype "passive"))
      (node (ref "U1") (pin "51") (pinfunction "PB12_51") (pintype "bidirectional"))
    )
    (net (code "12") (name "BATSTA") (class "Default")
      (node (ref "R23") (pin "2") (pinfunction "2_2") (pintype "passive"))
      (node (ref "U1") (pin "52") (pinfunction "PB13_52") (pintype "bidirectional"))
    )
    (net (code "13") (name "BOOT0@SYS") (class "Default")
      (node (ref "R17") (pin "1") (pinfunction "1_1") (pintype "passive"))
      (node (ref "S1") (pin "10") (pinfunction "10_10") (pintype "passive"))
      (node (ref "U1") (pin "94") (pinfunction "BOOT0_94") (pintype "input"))
    )
    (net (code "14") (name "BOOT1@SYS") (class "Default")
      (node (ref "R18") (pin "1") (pinfunction "1_1") (pintype "passive"))
      (node (ref "S1") (pin "9") (pinfunction "9_9") (pintype "passive"))
      (node (ref "U1") (pin "37") (pinfunction "PB2_37") (pintype "bidirectional"))
    )
    (net (code "15") (name "C1@ANA") (class "Default")
      (node (ref "C22") (pin "1") (pinfunction "1_1") (pintype "passive"))
      (node (ref "R33") (pin "2") (pinfunction "2_2") (pintype "passive"))
      (node (ref "U1") (pin "29") (pinfunction "PA4_29") (pintype "bidirectional"))
    )
    (net (code "16") (name "C2@ANA") (class "Default")
      (node (ref "C27") (pin "1") (pinfunction "1_1") (pintype "passive"))
      (node (ref "R64") (pin "2") (pinfunction "2_2") (pintype "passive"))
      (node (ref "U1") (pin "30") (pinfunction "PA5_30") (pintype "bidirectional"))
    )
    (net (code "17") (name "C3@ANA") (class "Default")
      (node (ref "C21") (pin "1") (pinfunction "1_1") (pintype "passive"))
      (node (ref "R32") (pin "2") (pinfunction "2_2") (pintype "passive"))
      (node (ref "U1") (pin "31") (pinfunction "PA6_31") (pintype "bidirectional"))
    )
    (net (code "18") (name "C4@ANA") (class "Default")
      (node (ref "C28") (pin "1") (pinfunction "1_1") (pintype "passive"))
      (node (ref "R65") (pin "2") (pinfunction "2_2") (pintype "passive"))
      (node (ref "U1") (pin "32") (pinfunction "PA7_32") (pintype "bidirectional"))
    )
    (net (code "19") (name "CD1") (class "Default")
      (node (ref "PD2") (pin "6") (pinfunction "CS_DIS_6") (pintype "input"))
      (node (ref "R37") (pin "2") (pinfunction "2_2") (pintype "passive"))
      (node (ref "U1") (pin "82") (pinfunction "PD1_82") (pintype "bidirectional"))
    )
    (net (code "20") (name "CD2") (class "Default")
      (node (ref "PD3") (pin "6") (pinfunction "CS_DIS_6") (pintype "input"))
      (node (ref "R68") (pin "2") (pinfunction "2_2") (pintype "passive"))
      (node (ref "U1") (pin "1") (pinfunction "PE2_1") (pintype "bidirectional"))
    )
    (net (code "21") (name "CD3") (class "Default")
      (node (ref "PD1") (pin "6") (pinfunction "CS_DIS_6") (pintype "input"))
      (node (ref "R36") (pin "2") (pinfunction "2_2") (pintype "passive"))
      (node (ref "U1") (pin "16") (pinfunction "PC1_16") (pintype "bidirectional"))
    )
    (net (code "22") (name "CD4") (class "Default")
      (node (ref "PD4") (pin "6") (pinfunction "CS_DIS_6") (pintype "input"))
      (node (ref "R69") (pin "2") (pinfunction "2_2") (pintype "passive"))
      (node (ref "U1") (pin "41") (pinfunction "PE10_41") (pintype "bidirectional"))
    )
    (net (code "23") (name "CLKIN") (class "Default")
      (node (ref "C8") (pin "2") (pinfunction "2_2") (pintype "passive"))
      (node (ref "U1") (pin "12") (pinfunction "OSC_IN_12") (pintype "input"))
      (node (ref "X2") (pin "1") (pinfunction "1_1") (pintype "passive"))
    )
    (net (code "24") (name "CLKOUT") (class "Default")
      (node (ref "C7") (pin "2") (pinfunction "2_2") (pintype "passive"))
      (node (ref "U1") (pin "13") (pinfunction "OSC_OUT_13") (pintype "output"))
      (node (ref "X2") (pin "2") (pinfunction "2_2") (pintype "passive"))
    )
    (net (code "25") (name "CTS2@UART") (class "Default")
      (node (ref "HD2") (pin "7") (pinfunction "7_7") (pintype "passive"))
      (node (ref "U1") (pin "84") (pinfunction "PD3_84") (pintype "bidirectional"))
    )
    (net (code "26") (name "DM@USB") (class "Default")
      (node (ref "U1") (pin "70") (pinfunction "PA_11_70") (pintype "bidirectional"))
      (node (ref "X1") (pin "2") (pinfunction "2_2") (pintype "input"))
    )
    (net (code "27") (name "DP@USB") (class "Default")
      (node (ref "U1") (pin "71") (pinfunction "PA_12_71") (pintype "bidirectional"))
      (node (ref "X1") (pin "3") (pinfunction "3_3") (pintype "input"))
    )
    (net (code "28") (name "EA1") (class "Default")
      (node (ref "PD2") (pin "5") (pinfunction "ENA/DIAGA_5") (pintype "input"))
      (node (ref "R45") (pin "1") (pinfunction "1_1") (pintype "passive"))
      (node (ref "U1") (pin "83") (pinfunction "PD2_83") (pintype "bidirectional"))
    )
    (net (code "29") (name "EA2") (class "Default")
      (node (ref "PD3") (pin "5") (pinfunction "ENA/DIAGA_5") (pintype "input"))
      (node (ref "R76") (pin "1") (pinfunction "1_1") (pintype "passive"))
      (node (ref "U1") (pin "2") (pinfunction "PE3_2") (pintype "bidirectional"))
    )
    (net (code "30") (name "EA3") (class "Default")
      (node (ref "PD1") (pin "5") (pinfunction "ENA/DIAGA_5") (pintype "input"))
      (node (ref "R44") (pin "1") (pinfunction "1_1") (pintype "passive"))
      (node (ref "U1") (pin "17") (pinfunction "PC2_17") (pintype "bidirectional"))
    )
    (net (code "31") (name "EA4") (class "Default")
      (node (ref "PD4") (pin "5") (pinfunction "ENA/DIAGA_5") (pintype "input"))
      (node (ref "R77") (pin "1") (pinfunction "1_1") (pintype "passive"))
      (node (ref "U1") (pin "43") (pinfunction "PE12_43") (pintype "bidirectional"))
    )
    (net (code "32") (name "EB1") (class "Default")
      (node (ref "PD2") (pin "9") (pinfunction "ENB/DIAGB_9") (pintype "input"))
      (node (ref "R41") (pin "1") (pinfunction "1_1") (pintype "passive"))
      (node (ref "U1") (pin "81") (pinfunction "PD0_81") (pintype "bidirectional"))
    )
    (net (code "33") (name "EB2") (class "Default")
      (node (ref "PD3") (pin "9") (pinfunction "ENB/DIAGB_9") (pintype "input"))
      (node (ref "R72") (pin "1") (pinfunction "1_1") (pintype "passive"))
      (node (ref "U1") (pin "98") (pinfunction "PE1_98") (pintype "bidirectional"))
    )
    (net (code "34") (name "EB3") (class "Default")
      (node (ref "PD1") (pin "9") (pinfunction "ENB/DIAGB_9") (pintype "input"))
      (node (ref "R40") (pin "1") (pinfunction "1_1") (pintype "passive"))
      (node (ref "U1") (pin "15") (pinfunction "PC0_15") (pintype "bidirectional"))
    )
    (net (code "35") (name "EB4") (class "Default")
      (node (ref "PD4") (pin "9") (pinfunction "ENB/DIAGB_9") (pintype "input"))
      (node (ref "R73") (pin "1") (pinfunction "1_1") (pintype "passive"))
      (node (ref "U1") (pin "39") (pinfunction "PE8_39") (pintype "bidirectional"))
    )
    (net (code "36") (name "EIO0") (class "Default")
      (node (ref "HD2") (pin "1") (pinfunction "1_1") (pintype "passive"))
      (node (ref "U1") (pin "79") (pinfunction "PC11_79") (pintype "bidirectional"))
    )
    (net (code "37") (name "EIO1") (class "Default")
      (node (ref "HD2") (pin "3") (pinfunction "3_3") (pintype "passive"))
      (node (ref "U1") (pin "78") (pinfunction "PC10_78") (pintype "bidirectional"))
    )
    (net (code "38") (name "ENCL1") (class "Default")
      (node (ref "R57") (pin "2") (pinfunction "2_2") (pintype "passive"))
      (node (ref "U1") (pin "92") (pinfunction "PB6_92") (pintype "bidirectional"))
    )
    (net (code "39") (name "ENCL2") (class "Default")
      (node (ref "R85") (pin "2") (pinfunction "2_2") (pintype "passive"))
      (node (ref "U1") (pin "7") (pinfunction "PC13-TAMPER-RTC_7") (pintype "bidirectional"))
    )
    (net (code "40") (name "ENCL3") (class "Default")
      (node (ref "R54") (pin "2") (pinfunction "2_2") (pintype "passive"))
      (node (ref "U1") (pin "35") (pinfunction "PB0_35") (pintype "bidirectional"))
    )
    (net (code "41") (name "ENCL4") (class "Default")
      (node (ref "R86") (pin "2") (pinfunction "2_2") (pintype "passive"))
      (node (ref "U1") (pin "45") (pinfunction "PE14_45") (pintype "bidirectional"))
    )
    (net (code "42") (name "ERR1") (class "Default")
      (node (ref "R53") (pin "2") (pinfunction "2_2") (pintype "passive"))
      (node (ref "U1") (pin "93") (pinfunction "PB7_93") (pintype "bidirectional"))
    )
    (net (code "43") (name "ERR2") (class "Default")
      (node (ref "R82") (pin "2") (pinfunction "2_2") (pintype "passive"))
      (node (ref "U1") (pin "8") (pinfunction "PC14-OSC32_IN_8") (pintype "bidirectional"))
    )
    (net (code "44") (name "ERR3") (class "Default")
      (node (ref "R49") (pin "2") (pinfunction "2_2") (pintype "passive"))
      (node (ref "U1") (pin "36") (pinfunction "PB1_36") (pintype "bidirectional"))
    )
    (net (code "45") (name "ERR4") (class "Default")
      (node (ref "R84") (pin "2") (pinfunction "2_2") (pintype "passive"))
      (node (ref "U1") (pin "46") (pinfunction "PE15_46") (pintype "bidirectional"))
    )
    (net (code "46") (name "GND") (class "Default")
      (node (ref "C1") (pin "2") (pinfunction "2_2") (pintype "passive"))
      (node (ref "C10") (pin "1") (pinfunction "1_1") (pintype "passive"))
      (node (ref "C11") (pin "1") (pinfunction "1_1") (pintype "passive"))
      (node (ref "C12") (pin "1") (pinfunction "1_1") (pintype "passive"))
      (node (ref "C13") (pin "1") (pinfunction "1_1") (pintype "passive"))
      (node (ref "C14") (pin "1") (pinfunction "1_1") (pintype "passive"))
      (node (ref "C15") (pin "1") (pinfunction "1_1") (pintype "passive"))
      (node (ref "C16") (pin "1") (pinfunction "1_1") (pintype "passive"))
      (node (ref "C17") (pin "1") (pinfunction "1_1") (pintype "passive"))
      (node (ref "C18") (pin "1") (pinfunction "1_1") (pintype "passive"))
      (node (ref "C19") (pin "1") (pinfunction "1_1") (pintype "passive"))
      (node (ref "C2") (pin "1") (pinfunction "1_1") (pintype "passive"))
      (node (ref "C20") (pin "1") (pinfunction "1_1") (pintype "passive"))
      (node (ref "C21") (pin "2") (pinfunction "2_2") (pintype "passive"))
      (node (ref "C22") (pin "2") (pinfunction "2_2") (pintype "passive"))
      (node (ref "C23") (pin "2") (pinfunction "2_2") (pintype "passive"))
      (node (ref "C24") (pin "2") (pinfunction "2_2") (pintype "passive"))
      (node (ref "C25") (pin "N") (pinfunction "N_N") (pintype "passive"))
      (node (ref "C26") (pin "N") (pinfunction "N_N") (pintype "passive"))
      (node (ref "C27") (pin "2") (pinfunction "2_2") (pintype "passive"))
      (node (ref "C28") (pin "2") (pinfunction "2_2") (pintype "passive"))
      (node (ref "C29") (pin "2") (pinfunction "2_2") (pintype "passive"))
      (node (ref "C3") (pin "2") (pinfunction "2_2") (pintype "passive"))
      (node (ref "C30") (pin "2") (pinfunction "2_2") (pintype "passive"))
      (node (ref "C31") (pin "N") (pinfunction "N_N") (pintype "passive"))
      (node (ref "C32") (pin "N") (pinfunction "N_N") (pintype "passive"))
      (node (ref "C33") (pin "2") (pinfunction "2_2") (pintype "passive"))
      (node (ref "C4") (pin "1") (pinfunction "1_1") (pintype "passive"))
      (node (ref "C5") (pin "1") (pinfunction "1_1") (pintype "passive"))
      (node (ref "C6") (pin "1") (pinfunction "1_1") (pintype "passive"))
      (node (ref "C7") (pin "1") (pinfunction "1_1") (pintype "passive"))
      (node (ref "C8") (pin "1") (pinfunction "1_1") (pintype "passive"))
      (node (ref "C9") (pin "1") (pinfunction "1_1") (pintype "passive"))
      (node (ref "CON1") (pin "P$2") (pinfunction "2_P$2") (pintype "passive"))
      (node (ref "CON2") (pin "P$2") (pinfunction "2_P$2") (pintype "passive"))
      (node (ref "CON3") (pin "P$2") (pinfunction "2_P$2") (pintype "passive"))
      (node (ref "CON4") (pin "P$2") (pinfunction "2_P$2") (pintype "passive"))
      (node (ref "HD1") (pin "2") (pinfunction "2_2") (pintype "passive"))
      (node (ref "HD2") (pin "4") (pinfunction "4_4") (pintype "passive"))
      (node (ref "IC1") (pin "2") (pinfunction "GND_2") (pintype "power_in"))
      (node (ref "IC2") (pin "2") (pinfunction "VSS_2") (pintype "bidirectional"))
      (node (ref "J1") (pin "3") (pinfunction "3_3") (pintype "passive"))
      (node (ref "J1") (pin "5") (pinfunction "5_5") (pintype "passive"))
      (node (ref "J1") (pin "9") (pinfunction "9_9") (pintype "passive"))
      (node (ref "LED1") (pin "K") (pinfunction "K_K") (pintype "passive"))
      (node (ref "LED10") (pin "K") (pinfunction "K_K") (pintype "passive"))
      (node (ref "LED11") (pin "K") (pinfunction "K_K") (pintype "passive"))
      (node (ref "LED12") (pin "K") (pinfunction "K_K") (pintype "passive"))
      (node (ref "LED2") (pin "K") (pinfunction "K_K") (pintype "passive"))
      (node (ref "LED3") (pin "K") (pinfunction "K_K") (pintype "passive"))
      (node (ref "LED4") (pin "K") (pinfunction "K_K") (pintype "passive"))
      (node (ref "LED5") (pin "K") (pinfunction "K_K") (pintype "passive"))
      (node (ref "LED6") (pin "K") (pinfunction "K_K") (pintype "passive"))
      (node (ref "LED7") (pin "K") (pinfunction "K_K") (pintype "passive"))
      (node (ref "LED8") (pin "K") (pinfunction "K_K") (pintype "passive"))
      (node (ref "LED9") (pin "K") (pinfunction "K_K") (pintype "passive"))
      (node (ref "PD1") (pin "18") (pinfunction "GNDB#1_18") (pintype "power_in"))
      (node (ref "PD1") (pin "19") (pinfunction "GNDB#2_19") (pintype "power_in"))
      (node (ref "PD1") (pin "20") (pinfunction "GNDB#3_20") (pintype "power_in"))
      (node (ref "PD1") (pin "26") (pinfunction "GNDA#1_26") (pintype "power_in"))
      (node (ref "PD1") (pin "27") (pinfunction "GNDA#2_27") (pintype "power_in"))
      (node (ref "PD1") (pin "28") (pinfunction "GNDA#3_28") (pintype "power_in"))
      (node (ref "PD2") (pin "18") (pinfunction "GNDB#1_18") (pintype "power_in"))
      (node (ref "PD2") (pin "19") (pinfunction "GNDB#2_19") (pintype "power_in"))
      (node (ref "PD2") (pin "20") (pinfunction "GNDB#3_20") (pintype "power_in"))
      (node (ref "PD2") (pin "26") (pinfunction "GNDA#1_26") (pintype "power_in"))
      (node (ref "PD2") (pin "27") (pinfunction "GNDA#2_27") (pintype "power_in"))
      (node (ref "PD2") (pin "28") (pinfunction "GNDA#3_28") (pintype "power_in"))
      (node (ref "PD3") (pin "18") (pinfunction "GNDB#1_18") (pintype "power_in"))
      (node (ref "PD3") (pin "19") (pinfunction "GNDB#2_19") (pintype "power_in"))
      (node (ref "PD3") (pin "20") (pinfunction "GNDB#3_20") (pintype "power_in"))
      (node (ref "PD3") (pin "26") (pinfunction "GNDA#1_26") (pintype "power_in"))
      (node (ref "PD3") (pin "27") (pinfunction "GNDA#2_27") (pintype "power_in"))
      (node (ref "PD3") (pin "28") (pinfunction "GNDA#3_28") (pintype "power_in"))
      (node (ref "PD4") (pin "18") (pinfunction "GNDB#1_18") (pintype "power_in"))
      (node (ref "PD4") (pin "19") (pinfunction "GNDB#2_19") (pintype "power_in"))
      (node (ref "PD4") (pin "20") (pinfunction "GNDB#3_20") (pintype "power_in"))
      (node (ref "PD4") (pin "26") (pinfunction "GNDA#1_26") (pintype "power_in"))
      (node (ref "PD4") (pin "27") (pinfunction "GNDA#2_27") (pintype "power_in"))
      (node (ref "PD4") (pin "28") (pinfunction "GNDA#3_28") (pintype "power_in"))
      (node (ref "R10") (pin "2") (pinfunction "2_2") (pintype "passive"))
      (node (ref "R34") (pin "1") (pinfunction "1_1") (pintype "passive"))
      (node (ref "R35") (pin "1") (pinfunction "1_1") (pintype "passive"))
      (node (ref "R36") (pin "1") (pinfunction "1_1") (pintype "passive"))
      (node (ref "R37") (pin "1") (pinfunction "1_1") (pintype "passive"))
      (node (ref "R38") (pin "1") (pinfunction "1_1") (pintype "passive"))
      (node (ref "R39") (pin "1") (pinfunction "1_1") (pintype "passive"))
      (node (ref "R42") (pin "1") (pinfunction "1_1") (pintype "passive"))
      (node (ref "R43") (pin "1") (pinfunction "1_1") (pintype "passive"))
      (node (ref "R46") (pin "1") (pinfunction "1_1") (pintype "passive"))
      (node (ref "R47") (pin "1") (pinfunction "1_1") (pintype "passive"))
      (node (ref "R66") (pin "1") (pinfunction "1_1") (pintype "passive"))
      (node (ref "R67") (pin "1") (pinfunction "1_1") (pintype "passive"))
      (node (ref "R68") (pin "1") (pinfunction "1_1") (pintype "passive"))
      (node (ref "R69") (pin "1") (pinfunction "1_1") (pintype "passive"))
      (node (ref "R70") (pin "1") (pinfunction "1_1") (pintype "passive"))
      (node (ref "R71") (pin "1") (pinfunction "1_1") (pintype "passive"))
      (node (ref "R74") (pin "1") (pinfunction "1_1") (pintype "passive"))
      (node (ref "R75") (pin "1") (pinfunction "1_1") (pintype "passive"))
      (node (ref "R78") (pin "1") (pinfunction "1_1") (pintype "passive"))
      (node (ref "R79") (pin "1") (pinfunction "1_1") (pintype "passive"))
      (node (ref "R91") (pin "1") (pinfunction "1_1") (pintype "passive"))
      (node (ref "S1") (pin "1") (pinfunction "1_1") (pintype "passive"))
      (node (ref "S1") (pin "2") (pinfunction "2_2") (pintype "passive"))
      (node (ref "S1") (pin "3") (pinfunction "3_3") (pintype "passive"))
      (node (ref "S1") (pin "4") (pinfunction "4_4") (pintype "passive"))
      (node (ref "S1") (pin "5") (pinfunction "5_5") (pintype "passive"))
      (node (ref "S1") (pin "6") (pinfunction "6_6") (pintype "passive"))
      (node (ref "S1") (pin "7") (pinfunction "7_7") (pintype "passive"))
      (node (ref "S1") (pin "8") (pinfunction "8_8") (pintype "passive"))
      (node (ref "SW1") (pin "2-1") (pinfunction "2-1_2-1") (pintype "passive"))
      (node (ref "SW1") (pin "2-2") (pinfunction "2-2_2-2") (pintype "passive"))
      (node (ref "SW2") (pin "2-1") (pinfunction "2-1_2-1") (pintype "passive"))
      (node (ref "SW2") (pin "2-2") (pinfunction "2-2_2-2") (pintype "passive"))
      (node (ref "SW3") (pin "2-1") (pinfunction "2-1_2-1") (pintype "passive"))
      (node (ref "SW3") (pin "2-2") (pinfunction "2-2_2-2") (pintype "passive"))
      (node (ref "U1") (pin "10") (pinfunction "VSS_5_10") (pintype "power_in"))
      (node (ref "U1") (pin "20") (pinfunction "VREF-_20") (pintype "power_in"))
      (node (ref "U1") (pin "27") (pinfunction "VSS_4_27") (pintype "power_in"))
      (node (ref "U1") (pin "49") (pinfunction "VSS_1_49") (pintype "power_in"))
      (node (ref "U1") (pin "74") (pinfunction "VSS_2_74") (pintype "power_in"))
      (node (ref "U1") (pin "99") (pinfunction "VSS_3_99") (pintype "power_in"))
      (node (ref "X1") (pin "5") (pinfunction "5_5") (pintype "input"))
    )
    (net (code "47") (name "KEY") (class "Default")
      (node (ref "J1") (pin "7") (pinfunction "7_7") (pintype "passive"))
    )
    (net (code "48") (name "M1M") (class "Default")
      (node (ref "PD2") (pin "15") (pinfunction "OUTB#1_15") (pintype "output"))
      (node (ref "PD2") (pin "16") (pinfunction "OUTB#2_16") (pintype "output"))
      (node (ref "PD2") (pin "21") (pinfunction "OUTB#3_21") (pintype "output"))
      (node (ref "PD2") (pin "OUTB#PAD") (pinfunction "OUTB#PAD_OUTB#PAD") (pintype "output"))
    )
    (net (code "49") (name "M1P") (class "Default")
      (node (ref "PD2") (pin "1") (pinfunction "OUTA#1_1") (pintype "output"))
      (node (ref "PD2") (pin "25") (pinfunction "OUTA#2_25") (pintype "output"))
      (node (ref "PD2") (pin "30") (pinfunction "OUTA#3_30") (pintype "output"))
      (node (ref "PD2") (pin "OUTA#PAD") (pinfunction "OUTA#PAD_OUTA#PAD") (pintype "output"))
    )
    (net (code "50") (name "M2M") (class "Default")
      (node (ref "PD3") (pin "15") (pinfunction "OUTB#1_15") (pintype "output"))
      (node (ref "PD3") (pin "16") (pinfunction "OUTB#2_16") (pintype "output"))
      (node (ref "PD3") (pin "21") (pinfunction "OUTB#3_21") (pintype "output"))
      (node (ref "PD3") (pin "OUTB#PAD") (pinfunction "OUTB#PAD_OUTB#PAD") (pintype "output"))
    )
    (net (code "51") (name "M2P") (class "Default")
      (node (ref "PD3") (pin "1") (pinfunction "OUTA#1_1") (pintype "output"))
      (node (ref "PD3") (pin "25") (pinfunction "OUTA#2_25") (pintype "output"))
      (node (ref "PD3") (pin "30") (pinfunction "OUTA#3_30") (pintype "output"))
      (node (ref "PD3") (pin "OUTA#PAD") (pinfunction "OUTA#PAD_OUTA#PAD") (pintype "output"))
    )
    (net (code "52") (name "M3M") (class "Default")
      (node (ref "PD1") (pin "15") (pinfunction "OUTB#1_15") (pintype "output"))
      (node (ref "PD1") (pin "16") (pinfunction "OUTB#2_16") (pintype "output"))
      (node (ref "PD1") (pin "21") (pinfunction "OUTB#3_21") (pintype "output"))
      (node (ref "PD1") (pin "OUTB#PAD") (pinfunction "OUTB#PAD_OUTB#PAD") (pintype "output"))
    )
    (net (code "53") (name "M3P") (class "Default")
      (node (ref "PD1") (pin "1") (pinfunction "OUTA#1_1") (pintype "output"))
      (node (ref "PD1") (pin "25") (pinfunction "OUTA#2_25") (pintype "output"))
      (node (ref "PD1") (pin "30") (pinfunction "OUTA#3_30") (pintype "output"))
      (node (ref "PD1") (pin "OUTA#PAD") (pinfunction "OUTA#PAD_OUTA#PAD") (pintype "output"))
    )
    (net (code "54") (name "M4M") (class "Default")
      (node (ref "PD4") (pin "15") (pinfunction "OUTB#1_15") (pintype "output"))
      (node (ref "PD4") (pin "16") (pinfunction "OUTB#2_16") (pintype "output"))
      (node (ref "PD4") (pin "21") (pinfunction "OUTB#3_21") (pintype "output"))
      (node (ref "PD4") (pin "OUTB#PAD") (pinfunction "OUTB#PAD_OUTB#PAD") (pintype "output"))
    )
    (net (code "55") (name "M4P") (class "Default")
      (node (ref "PD4") (pin "1") (pinfunction "OUTA#1_1") (pintype "output"))
      (node (ref "PD4") (pin "25") (pinfunction "OUTA#2_25") (pintype "output"))
      (node (ref "PD4") (pin "30") (pinfunction "OUTA#3_30") (pintype "output"))
      (node (ref "PD4") (pin "OUTA#PAD") (pinfunction "OUTA#PAD_OUTA#PAD") (pintype "output"))
    )
    (net (code "56") (name "NRST@SYS") (class "Default")
      (node (ref "R14") (pin "2") (pinfunction "2_2") (pintype "passive"))
      (node (ref "U1") (pin "14") (pinfunction "NRST_14") (pintype "bidirectional"))
    )
    (net (code "57") (name "Net-(C2-Pad2)") (class "Default")
      (node (ref "C2") (pin "2") (pinfunction "2_2") (pintype "passive"))
      (node (ref "R1") (pin "2") (pinfunction "2_2") (pintype "passive"))
      (node (ref "R2") (pin "2") (pinfunction "2_2") (pintype "passive"))
      (node (ref "R3") (pin "1") (pinfunction "1_1") (pintype "passive"))
    )
    (net (code "58") (name "Net-(C4-Pad2)") (class "Default")
      (node (ref "C4") (pin "2") (pinfunction "2_2") (pintype "passive"))
      (node (ref "R14") (pin "1") (pinfunction "1_1") (pintype "passive"))
      (node (ref "R5") (pin "2") (pinfunction "2_2") (pintype "passive"))
      (node (ref "R8") (pin "2") (pinfunction "2_2") (pintype "passive"))
    )
    (net (code "59") (name "Net-(C5-Pad2)") (class "Default")
      (node (ref "C5") (pin "2") (pinfunction "2_2") (pintype "passive"))
      (node (ref "R16") (pin "1") (pinfunction "1_1") (pintype "passive"))
      (node (ref "R4") (pin "2") (pinfunction "2_2") (pintype "passive"))
      (node (ref "R9") (pin "2") (pinfunction "2_2") (pintype "passive"))
    )
    (net (code "60") (name "Net-(C6-Pad2)") (class "Default")
      (node (ref "C6") (pin "2") (pinfunction "2_2") (pintype "passive"))
      (node (ref "R10") (pin "1") (pinfunction "1_1") (pintype "passive"))
      (node (ref "R19") (pin "1") (pinfunction "1_1") (pintype "passive"))
      (node (ref "RV1") (pin "2") (pinfunction "2_2") (pintype "bidirectional"))
      (node (ref "RV1") (pin "3") (pinfunction "3_3") (pintype "passive"))
    )
    (net (code "61") (name "Net-(D1-PadA)") (class "Default")
      (node (ref "D1") (pin "A") (pinfunction "A_A") (pintype "passive"))
      (node (ref "HD1") (pin "1") (pinfunction "1_1") (pintype "passive"))
    )
    (net (code "62") (name "Net-(D2-PadA)") (class "Default")
      (node (ref "D2") (pin "A") (pinfunction "A_A") (pintype "passive"))
      (node (ref "X1") (pin "1") (pinfunction "1_1") (pintype "input"))
    )
    (net (code "63") (name "Net-(IC2-VREF)") (class "Default")
      (node (ref "C9") (pin "2") (pinfunction "2_2") (pintype "passive"))
      (node (ref "IC2") (pin "1") (pinfunction "VREF_1") (pintype "bidirectional"))
      (node (ref "R22") (pin "2") (pinfunction "2_2") (pintype "passive"))
      (node (ref "U1") (pin "21") (pinfunction "VREF+_21") (pintype "power_in"))
    )
    (net (code "64") (name "Net-(LED1-PadA)") (class "Default")
      (node (ref "LED1") (pin "A") (pinfunction "A_A") (pintype "passive"))
      (node (ref "R20") (pin "1") (pinfunction "1_1") (pintype "passive"))
    )
    (net (code "65") (name "Net-(LED2-PadA)") (class "Default")
      (node (ref "LED2") (pin "A") (pinfunction "A_A") (pintype "passive"))
      (node (ref "R21") (pin "1") (pinfunction "1_1") (pintype "passive"))
    )
    (net (code "66") (name "Net-(LED3-PadA)") (class "Default")
      (node (ref "LED3") (pin "A") (pinfunction "A_A") (pintype "passive"))
      (node (ref "R23") (pin "1") (pinfunction "1_1") (pintype "passive"))
    )
    (net (code "67") (name "Net-(LED4-PadA)") (class "Default")
      (node (ref "LED4") (pin "A") (pinfunction "A_A") (pintype "passive"))
      (node (ref "R24") (pin "1") (pinfunction "1_1") (pintype "passive"))
    )
    (net (code "68") (name "Net-(LED5-PadA)") (class "Default")
      (node (ref "LED5") (pin "A") (pinfunction "A_A") (pintype "passive"))
      (node (ref "R49") (pin "1") (pinfunction "1_1") (pintype "passive"))
    )
    (net (code "69") (name "Net-(LED6-PadA)") (class "Default")
      (node (ref "LED6") (pin "A") (pinfunction "A_A") (pintype "passive"))
      (node (ref "R53") (pin "1") (pinfunction "1_1") (pintype "passive"))
    )
    (net (code "70") (name "Net-(LED7-PadA)") (class "Default")
      (node (ref "LED7") (pin "A") (pinfunction "A_A") (pintype "passive"))
      (node (ref "R54") (pin "1") (pinfunction "1_1") (pintype "passive"))
    )
    (net (code "71") (name "Net-(LED8-PadA)") (class "Default")
      (node (ref "LED8") (pin "A") (pinfunction "A_A") (pintype "passive"))
      (node (ref "R57") (pin "1") (pinfunction "1_1") (pintype "passive"))
    )
    (net (code "72") (name "Net-(LED9-PadA)") (class "Default")
      (node (ref "LED9") (pin "A") (pinfunction "A_A") (pintype "passive"))
      (node (ref "R82") (pin "1") (pinfunction "1_1") (pintype "passive"))
    )
    (net (code "73") (name "Net-(LED10-PadA)") (class "Default")
      (node (ref "LED10") (pin "A") (pinfunction "A_A") (pintype "passive"))
      (node (ref "R84") (pin "1") (pinfunction "1_1") (pintype "passive"))
    )
    (net (code "74") (name "Net-(LED11-PadA)") (class "Default")
      (node (ref "LED11") (pin "A") (pinfunction "A_A") (pintype "passive"))
      (node (ref "R85") (pin "1") (pinfunction "1_1") (pintype "passive"))
    )
    (net (code "75") (name "Net-(LED12-PadA)") (class "Default")
      (node (ref "LED12") (pin "A") (pinfunction "A_A") (pintype "passive"))
      (node (ref "R86") (pin "1") (pinfunction "1_1") (pintype "passive"))
    )
    (net (code "76") (name "Net-(PD1-CS)") (class "Default")
      (node (ref "PD1") (pin "8") (pinfunction "CS_8") (pintype "output"))
      (node (ref "R32") (pin "1") (pinfunction "1_1") (pintype "passive"))
      (node (ref "R34") (pin "2") (pinfunction "2_2") (pintype "passive"))
    )
    (net (code "77") (name "Net-(PD1-INA)") (class "Default")
      (node (ref "PD1") (pin "4") (pinfunction "INA_4") (pintype "input"))
      (node (ref "R27") (pin "2") (pinfunction "2_2") (pintype "passive"))
      (node (ref "R42") (pin "2") (pinfunction "2_2") (pintype "passive"))
    )
    (net (code "78") (name "Net-(PD1-INB)") (class "Default")
      (node (ref "PD1") (pin "10") (pinfunction "INB_10") (pintype "input"))
      (node (ref "R28") (pin "2") (pinfunction "2_2") (pintype "passive"))
      (node (ref "R38") (pin "2") (pinfunction "2_2") (pintype "passive"))
    )
    (net (code "79") (name "Net-(PD1-PWM)") (class "Default")
      (node (ref "PD1") (pin "7") (pinfunction "PWM_7") (pintype "input"))
      (node (ref "R26") (pin "2") (pinfunction "2_2") (pintype "passive"))
      (node (ref "R46") (pin "2") (pinfunction "2_2") (pintype "passive"))
    )
    (net (code "80") (name "Net-(PD2-CS)") (class "Default")
      (node (ref "PD2") (pin "8") (pinfunction "CS_8") (pintype "output"))
      (node (ref "R33") (pin "1") (pinfunction "1_1") (pintype "passive"))
      (node (ref "R35") (pin "2") (pinfunction "2_2") (pintype "passive"))
    )
    (net (code "81") (name "Net-(PD2-INA)") (class "Default")
      (node (ref "PD2") (pin "4") (pinfunction "INA_4") (pintype "input"))
      (node (ref "R30") (pin "2") (pinfunction "2_2") (pintype "passive"))
      (node (ref "R43") (pin "2") (pinfunction "2_2") (pintype "passive"))
    )
    (net (code "82") (name "Net-(PD2-INB)") (class "Default")
      (node (ref "PD2") (pin "10") (pinfunction "INB_10") (pintype "input"))
      (node (ref "R31") (pin "2") (pinfunction "2_2") (pintype "passive"))
      (node (ref "R39") (pin "2") (pinfunction "2_2") (pintype "passive"))
    )
    (net (code "83") (name "Net-(PD2-PWM)") (class "Default")
      (node (ref "PD2") (pin "7") (pinfunction "PWM_7") (pintype "input"))
      (node (ref "R29") (pin "2") (pinfunction "2_2") (pintype "passive"))
      (node (ref "R47") (pin "2") (pinfunction "2_2") (pintype "passive"))
    )
    (net (code "84") (name "Net-(PD3-CS)") (class "Default")
      (node (ref "PD3") (pin "8") (pinfunction "CS_8") (pintype "output"))
      (node (ref "R64") (pin "1") (pinfunction "1_1") (pintype "passive"))
      (node (ref "R66") (pin "2") (pinfunction "2_2") (pintype "passive"))
    )
    (net (code "85") (name "Net-(PD3-INA)") (class "Default")
      (node (ref "PD3") (pin "4") (pinfunction "INA_4") (pintype "input"))
      (node (ref "R60") (pin "2") (pinfunction "2_2") (pintype "passive"))
      (node (ref "R74") (pin "2") (pinfunction "2_2") (pintype "passive"))
    )
    (net (code "86") (name "Net-(PD3-INB)") (class "Default")
      (node (ref "PD3") (pin "10") (pinfunction "INB_10") (pintype "input"))
      (node (ref "R61") (pin "2") (pinfunction "2_2") (pintype "passive"))
      (node (ref "R70") (pin "2") (pinfunction "2_2") (pintype "passive"))
    )
    (net (code "87") (name "Net-(PD3-PWM)") (class "Default")
      (node (ref "PD3") (pin "7") (pinfunction "PWM_7") (pintype "input"))
      (node (ref "R59") (pin "2") (pinfunction "2_2") (pintype "passive"))
      (node (ref "R78") (pin "2") (pinfunction "2_2") (pintype "passive"))
    )
    (net (code "88") (name "Net-(PD4-CS)") (class "Default")
      (node (ref "PD4") (pin "8") (pinfunction "CS_8") (pintype "output"))
      (node (ref "R65") (pin "1") (pinfunction "1_1") (pintype "passive"))
      (node (ref "R67") (pin "2") (pinfunction "2_2") (pintype "passive"))
    )
    (net (code "89") (name "Net-(PD4-INA)") (class "Default")
      (node (ref "PD4") (pin "4") (pinfunction "INA_4") (pintype "input"))
      (node (ref "R63") (pin "2") (pinfunction "2_2") (pintype "passive"))
      (node (ref "R75") (pin "2") (pinfunction "2_2") (pintype "passive"))
    )
    (net (code "90") (name "Net-(PD4-INB)") (class "Default")
      (node (ref "PD4") (pin "10") (pinfunction "INB_10") (pintype "input"))
      (node (ref "R58") (pin "2") (pinfunction "2_2") (pintype "passive"))
      (node (ref "R71") (pin "2") (pinfunction "2_2") (pintype "passive"))
    )
    (net (code "91") (name "Net-(PD4-PWM)") (class "Default")
      (node (ref "PD4") (pin "7") (pinfunction "PWM_7") (pintype "input"))
      (node (ref "R62") (pin "2") (pinfunction "2_2") (pintype "passive"))
      (node (ref "R79") (pin "2") (pinfunction "2_2") (pintype "passive"))
    )
    (net (code "92") (name "Net-(R1-Pad1)") (class "Default")
      (node (ref "R1") (pin "1") (pinfunction "1_1") (pintype "passive"))
      (node (ref "SW1") (pin "1-1") (pinfunction "1-1_1-1") (pintype "passive"))
      (node (ref "SW1") (pin "1-2") (pinfunction "1-2_1-2") (pintype "passive"))
    )
    (net (code "93") (name "Net-(R4-Pad1)") (class "Default")
      (node (ref "R4") (pin "1") (pinfunction "1_1") (pintype "passive"))
      (node (ref "SW2") (pin "1-1") (pinfunction "1-1_1-1") (pintype "passive"))
      (node (ref "SW2") (pin "1-2") (pinfunction "1-2_1-2") (pintype "passive"))
    )
    (net (code "94") (name "Net-(R5-Pad1)") (class "Default")
      (node (ref "R5") (pin "1") (pinfunction "1_1") (pintype "passive"))
      (node (ref "SW3") (pin "1-1") (pinfunction "1-1_1-1") (pintype "passive"))
      (node (ref "SW3") (pin "1-2") (pinfunction "1-2_1-2") (pintype "passive"))
    )
    (net (code "95") (name "Net-(R90-Pad1)") (class "Default")
      (node (ref "R90") (pin "1") (pinfunction "1_1") (pintype "passive"))
      (node (ref "R91") (pin "2") (pinfunction "2_2") (pintype "passive"))
      (node (ref "R92") (pin "2") (pinfunction "2_2") (pintype "passive"))
    )
    (net (code "96") (name "Net-(U1-VCAP_1)") (class "Default")
      (node (ref "C11") (pin "2") (pinfunction "2_2") (pintype "passive"))
      (node (ref "U1") (pin "48") (pinfunction "VCAP_1_48") (pintype "bidirectional"))
    )
    (net (code "97") (name "Net-(U1-VCAP_2)") (class "Default")
      (node (ref "C20") (pin "2") (pinfunction "2_2") (pintype "passive"))
      (node (ref "U1") (pin "73") (pinfunction "VCAP_2_73") (pintype "power_in"))
    )
    (net (code "98") (name "Net-(U1-VSSA)") (class "Default")
      (node (ref "C10") (pin "2") (pinfunction "2_2") (pintype "passive"))
      (node (ref "R25") (pin "1") (pinfunction "1_1") (pintype "passive"))
      (node (ref "U1") (pin "19") (pinfunction "VSSA_19") (pintype "power_in"))
    )
    (net (code "99") (name "P1@PWM") (class "Default")
      (node (ref "R29") (pin "1") (pinfunction "1_1") (pintype "passive"))
      (node (ref "U1") (pin "95") (pinfunction "PB8_95") (pintype "bidirectional"))
    )
    (net (code "100") (name "P2@PWM") (class "Default")
      (node (ref "R59") (pin "1") (pinfunction "1_1") (pintype "passive"))
      (node (ref "U1") (pin "96") (pinfunction "PB9_96") (pintype "bidirectional"))
    )
    (net (code "101") (name "P3@PWM") (class "Default")
      (node (ref "R26") (pin "1") (pinfunction "1_1") (pintype "passive"))
      (node (ref "U1") (pin "5") (pinfunction "PE6_5") (pintype "bidirectional"))
    )
    (net (code "102") (name "P4@PWM") (class "Default")
      (node (ref "R62") (pin "1") (pinfunction "1_1") (pintype "passive"))
      (node (ref "U1") (pin "4") (pinfunction "PE5_4") (pintype "bidirectional"))
    )
    (net (code "103") (name "RTS2@UART") (class "Default")
      (node (ref "HD2") (pin "5") (pinfunction "5_5") (pintype "passive"))
      (node (ref "U1") (pin "85") (pinfunction "PD4_85") (pintype "bidirectional"))
    )
    (net (code "104") (name "RX1@UART") (class "Default")
      (node (ref "HD1") (pin "3") (pinfunction "3_3") (pintype "passive"))
      (node (ref "U1") (pin "26") (pinfunction "PA3_26") (pintype "bidirectional"))
    )
    (net (code "105") (name "RX2@UART") (class "Default")
      (node (ref "HD2") (pin "6") (pinfunction "6_6") (pintype "passive"))
      (node (ref "U1") (pin "87") (pinfunction "PD6_87") (pintype "bidirectional"))
    )
    (net (code "106") (name "RXSTA") (class "Default")
      (node (ref "R21") (pin "2") (pinfunction "2_2") (pintype "passive"))
      (node (ref "U1") (pin "53") (pinfunction "PB14_53") (pintype "bidirectional"))
    )
    (net (code "107") (name "SA0") (class "Default")
      (node (ref "R6") (pin "1") (pinfunction "1_1") (pintype "passive"))
      (node (ref "S1") (pin "16") (pinfunction "16_16") (pintype "passive"))
      (node (ref "U1") (pin "68") (pinfunction "PA_9_68") (pintype "bidirectional"))
    )
    (net (code "108") (name "SA1") (class "Default")
      (node (ref "R7") (pin "1") (pinfunction "1_1") (pintype "passive"))
      (node (ref "S1") (pin "15") (pinfunction "15_15") (pintype "passive"))
      (node (ref "U1") (pin "67") (pinfunction "PA_8_67") (pintype "bidirectional"))
    )
    (net (code "109") (name "SA2") (class "Default")
      (node (ref "R11") (pin "1") (pinfunction "1_1") (pintype "passive"))
      (node (ref "S1") (pin "14") (pinfunction "14_14") (pintype "passive"))
      (node (ref "U1") (pin "66") (pinfunction "PC9_66") (pintype "bidirectional"))
    )
    (net (code "110") (name "SA3") (class "Default")
      (node (ref "R12") (pin "1") (pinfunction "1_1") (pintype "passive"))
      (node (ref "S1") (pin "13") (pinfunction "13_13") (pintype "passive"))
      (node (ref "U1") (pin "65") (pinfunction "PC8_65") (pintype "bidirectional"))
    )
    (net (code "111") (name "SB0") (class "Default")
      (node (ref "R13") (pin "1") (pinfunction "1_1") (pintype "passive"))
      (node (ref "S1") (pin "12") (pinfunction "12_12") (pintype "passive"))
      (node (ref "U1") (pin "62") (pinfunction "PD15_62") (pintype "bidirectional"))
    )
    (net (code "112") (name "SB1") (class "Default")
      (node (ref "R15") (pin "1") (pinfunction "1_1") (pintype "passive"))
      (node (ref "S1") (pin "11") (pinfunction "11_11") (pintype "passive"))
      (node (ref "U1") (pin "61") (pinfunction "PD14_61") (pintype "bidirectional"))
    )
    (net (code "113") (name "SW0") (class "Default")
      (node (ref "R16") (pin "2") (pinfunction "2_2") (pintype "passive"))
      (node (ref "U1") (pin "91") (pinfunction "PB5_91") (pintype "bidirectional"))
    )
    (net (code "114") (name "SW1") (class "Default")
      (node (ref "R3") (pin "2") (pinfunction "2_2") (pintype "passive"))
      (node (ref "U1") (pin "47") (pinfunction "PB10_47") (pintype "bidirectional"))
    )
    (net (code "115") (name "TCK") (class "Default")
      (node (ref "J1") (pin "4") (pinfunction "4_4") (pintype "passive"))
      (node (ref "U1") (pin "76") (pinfunction "PA14_76") (pintype "bidirectional"))
    )
    (net (code "116") (name "TDI") (class "Default")
      (node (ref "J1") (pin "8") (pinfunction "8_8") (pintype "passive"))
      (node (ref "U1") (pin "77") (pinfunction "PA15_77") (pintype "bidirectional"))
    )
    (net (code "117") (name "TDO") (class "Default")
      (node (ref "J1") (pin "6") (pinfunction "6_6") (pintype "passive"))
      (node (ref "U1") (pin "89") (pinfunction "PB3_89") (pintype "bidirectional"))
    )
    (net (code "118") (name "TMS") (class "Default")
      (node (ref "J1") (pin "2") (pinfunction "2_2") (pintype "passive"))
      (node (ref "U1") (pin "72") (pinfunction "PA_13_72") (pintype "bidirectional"))
    )
    (net (code "119") (name "TRST") (class "Default")
      (node (ref "J1") (pin "10") (pinfunction "10_10") (pintype "passive"))
      (node (ref "U1") (pin "90") (pinfunction "PB4_90") (pintype "bidirectional"))
    )
    (net (code "120") (name "TX1@UART") (class "Default")
      (node (ref "HD1") (pin "4") (pinfunction "4_4") (pintype "passive"))
      (node (ref "U1") (pin "25") (pinfunction "PA2_25") (pintype "bidirectional"))
    )
    (net (code "121") (name "TX2@UART") (class "Default")
      (node (ref "HD2") (pin "8") (pinfunction "8_8") (pintype "passive"))
      (node (ref "U1") (pin "86") (pinfunction "PD5_86") (pintype "bidirectional"))
    )
    (net (code "122") (name "TXSTA") (class "Default")
      (node (ref "R20") (pin "2") (pinfunction "2_2") (pintype "passive"))
      (node (ref "U1") (pin "54") (pinfunction "PB15_54") (pintype "bidirectional"))
    )
    (net (code "123") (name "USB_ID") (class "Default")
      (node (ref "X1") (pin "4") (pinfunction "4_4") (pintype "input"))
    )
    (net (code "124") (name "V+") (class "Default")
      (node (ref "C23") (pin "1") (pinfunction "1_1") (pintype "passive"))
      (node (ref "C24") (pin "1") (pinfunction "1_1") (pintype "passive"))
      (node (ref "C25") (pin "P") (pinfunction "P_P") (pintype "passive"))
      (node (ref "C26") (pin "P") (pinfunction "P_P") (pintype "passive"))
      (node (ref "C29") (pin "1") (pinfunction "1_1") (pintype "passive"))
      (node (ref "C30") (pin "1") (pinfunction "1_1") (pintype "passive"))
      (node (ref "C31") (pin "P") (pinfunction "P_P") (pintype "passive"))
      (node (ref "C32") (pin "P") (pinfunction "P_P") (pintype "passive"))
      (node (ref "PD1") (pin "12") (pinfunction "VBAT_12") (pintype "power_in"))
      (node (ref "PD1") (pin "13") (pinfunction "VCC#2_13") (pintype "power_in"))
      (node (ref "PD1") (pin "23") (pinfunction "VCC#3_23") (pintype "power_in"))
      (node (ref "PD1") (pin "3") (pinfunction "VCC#1_3") (pintype "power_in"))
      (node (ref "PD1") (pin "VCC#PAD") (pinfunction "VCC#PAD_VCC#PAD") (pintype "power_in"))
      (node (ref "PD2") (pin "12") (pinfunction "VBAT_12") (pintype "power_in"))
      (node (ref "PD2") (pin "13") (pinfunction "VCC#2_13") (pintype "power_in"))
      (node (ref "PD2") (pin "23") (pinfunction "VCC#3_23") (pintype "power_in"))
      (node (ref "PD2") (pin "3") (pinfunction "VCC#1_3") (pintype "power_in"))
      (node (ref "PD2") (pin "VCC#PAD") (pinfunction "VCC#PAD_VCC#PAD") (pintype "power_in"))
      (node (ref "PD3") (pin "12") (pinfunction "VBAT_12") (pintype "power_in"))
      (node (ref "PD3") (pin "13") (pinfunction "VCC#2_13") (pintype "power_in"))
      (node (ref "PD3") (pin "23") (pinfunction "VCC#3_23") (pintype "power_in"))
      (node (ref "PD3") (pin "3") (pinfunction "VCC#1_3") (pintype "power_in"))
      (node (ref "PD3") (pin "VCC#PAD") (pinfunction "VCC#PAD_VCC#PAD") (pintype "power_in"))
      (node (ref "PD4") (pin "12") (pinfunction "VBAT_12") (pintype "power_in"))
      (node (ref "PD4") (pin "13") (pinfunction "VCC#2_13") (pintype "power_in"))
      (node (ref "PD4") (pin "23") (pinfunction "VCC#3_23") (pintype "power_in"))
      (node (ref "PD4") (pin "3") (pinfunction "VCC#1_3") (pintype "power_in"))
      (node (ref "PD4") (pin "VCC#PAD") (pinfunction "VCC#PAD_VCC#PAD") (pintype "power_in"))
      (node (ref "R90") (pin "2") (pinfunction "2_2") (pintype "passive"))
    )
    (net (code "125") (name "VM@ANA") (class "Default")
      (node (ref "C33") (pin "1") (pinfunction "1_1") (pintype "passive"))
      (node (ref "R92") (pin "1") (pinfunction "1_1") (pintype "passive"))
      (node (ref "U1") (pin "33") (pinfunction "PC4_33") (pintype "bidirectional"))
    )
    (net (code "126") (name "VT@ANA") (class "Default")
      (node (ref "R19") (pin "2") (pinfunction "2_2") (pintype "passive"))
      (node (ref "U1") (pin "34") (pinfunction "PC5_34") (pintype "bidirectional"))
    )
    (net (code "127") (name "X1@ENC") (class "Default")
      (node (ref "CON1") (pin "P$3") (pinfunction "3_P$3") (pintype "passive"))
      (node (ref "R48") (pin "1") (pinfunction "1_1") (pintype "passive"))
      (node (ref "U1") (pin "63") (pinfunction "PC6_63") (pintype "bidirectional"))
    )
    (net (code "128") (name "X2@ENC") (class "Default")
      (node (ref "CON3") (pin "P$3") (pinfunction "3_P$3") (pintype "passive"))
      (node (ref "R80") (pin "1") (pinfunction "1_1") (pintype "passive"))
      (node (ref "U1") (pin "59") (pinfunction "PD12_59") (pintype "bidirectional"))
    )
    (net (code "129") (name "X3@ENC") (class "Default")
      (node (ref "CON2") (pin "P$3") (pinfunction "3_P$3") (pintype "passive"))
      (node (ref "R50") (pin "1") (pinfunction "1_1") (pintype "passive"))
      (node (ref "U1") (pin "40") (pinfunction "PE9_40") (pintype "bidirectional"))
    )
    (net (code "130") (name "X4@ENC") (class "Default")
      (node (ref "CON4") (pin "P$3") (pinfunction "3_P$3") (pintype "passive"))
      (node (ref "R87") (pin "1") (pinfunction "1_1") (pintype "passive"))
      (node (ref "U1") (pin "23") (pinfunction "PA0-WKUP_23") (pintype "bidirectional"))
    )
    (net (code "131") (name "Y1@ENC") (class "Default")
      (node (ref "CON1") (pin "P$4") (pinfunction "4_P$4") (pintype "passive"))
      (node (ref "R51") (pin "1") (pinfunction "1_1") (pintype "passive"))
      (node (ref "U1") (pin "64") (pinfunction "PC7_64") (pintype "bidirectional"))
    )
    (net (code "132") (name "Y2@ENC") (class "Default")
      (node (ref "CON3") (pin "P$4") (pinfunction "4_P$4") (pintype "passive"))
      (node (ref "R81") (pin "1") (pinfunction "1_1") (pintype "passive"))
      (node (ref "U1") (pin "60") (pinfunction "PD13_60") (pintype "bidirectional"))
    )
    (net (code "133") (name "Y3@ENC") (class "Default")
      (node (ref "CON2") (pin "P$4") (pinfunction "4_P$4") (pintype "passive"))
      (node (ref "R52") (pin "1") (pinfunction "1_1") (pintype "passive"))
      (node (ref "U1") (pin "42") (pinfunction "PE11_42") (pintype "bidirectional"))
    )
    (net (code "134") (name "Y4@ENC") (class "Default")
      (node (ref "CON4") (pin "P$4") (pinfunction "4_P$4") (pintype "passive"))
      (node (ref "R88") (pin "1") (pinfunction "1_1") (pintype "passive"))
      (node (ref "U1") (pin "24") (pinfunction "PA1_24") (pintype "bidirectional"))
    )
    (net (code "135") (name "Z1") (class "Default")
      (node (ref "CON1") (pin "P$5") (pinfunction "5_P$5") (pintype "passive"))
      (node (ref "R55") (pin "1") (pinfunction "1_1") (pintype "passive"))
      (node (ref "U1") (pin "58") (pinfunction "PD11_58") (pintype "bidirectional"))
    )
    (net (code "136") (name "Z2") (class "Default")
      (node (ref "CON3") (pin "P$5") (pinfunction "5_P$5") (pintype "passive"))
      (node (ref "R83") (pin "1") (pinfunction "1_1") (pintype "passive"))
      (node (ref "U1") (pin "57") (pinfunction "PD10_57") (pintype "bidirectional"))
    )
    (net (code "137") (name "Z3") (class "Default")
      (node (ref "CON2") (pin "P$5") (pinfunction "5_P$5") (pintype "passive"))
      (node (ref "R56") (pin "1") (pinfunction "1_1") (pintype "passive"))
      (node (ref "U1") (pin "56") (pinfunction "PD9_56") (pintype "bidirectional"))
    )
    (net (code "138") (name "Z4") (class "Default")
      (node (ref "CON4") (pin "P$5") (pinfunction "5_P$5") (pintype "passive"))
      (node (ref "R89") (pin "1") (pinfunction "1_1") (pintype "passive"))
      (node (ref "U1") (pin "55") (pinfunction "PD8_55") (pintype "bidirectional"))
    )
    (net (code "139") (name "unconnected-(IC1-NC-Pad4)") (class "Default")
      (node (ref "IC1") (pin "4") (pinfunction "NC_4") (pintype "no_connect"))
    )
    (net (code "140") (name "unconnected-(IC2-NC-Pad3)") (class "Default")
      (node (ref "IC2") (pin "3") (pinfunction "NC_3") (pintype "bidirectional"))
    )
    (net (code "141") (name "unconnected-(PD1-CP-Pad11)") (class "Default")
      (node (ref "PD1") (pin "11") (pinfunction "CP_11") (pintype "output"))
    )
    (net (code "142") (name "unconnected-(PD1-NC#1-Pad2)") (class "Default")
      (node (ref "PD1") (pin "2") (pinfunction "NC#1_2") (pintype "no_connect"))
    )
    (net (code "143") (name "unconnected-(PD1-NC#2-Pad14)") (class "Default")
      (node (ref "PD1") (pin "14") (pinfunction "NC#2_14") (pintype "no_connect"))
    )
    (net (code "144") (name "unconnected-(PD1-NC#3-Pad17)") (class "Default")
      (node (ref "PD1") (pin "17") (pinfunction "NC#3_17") (pintype "no_connect"))
    )
    (net (code "145") (name "unconnected-(PD1-NC#4-Pad22)") (class "Default")
      (node (ref "PD1") (pin "22") (pinfunction "NC#4_22") (pintype "no_connect"))
    )
    (net (code "146") (name "unconnected-(PD1-NC#5-Pad24)") (class "Default")
      (node (ref "PD1") (pin "24") (pinfunction "NC#5_24") (pintype "no_connect"))
    )
    (net (code "147") (name "unconnected-(PD1-NC#6-Pad29)") (class "Default")
      (node (ref "PD1") (pin "29") (pinfunction "NC#6_29") (pintype "no_connect"))
    )
    (net (code "148") (name "unconnected-(PD2-CP-Pad11)") (class "Default")
      (node (ref "PD2") (pin "11") (pinfunction "CP_11") (pintype "output"))
    )
    (net (code "149") (name "unconnected-(PD2-NC#1-Pad2)") (class "Default")
      (node (ref "PD2") (pin "2") (pinfunction "NC#1_2") (pintype "no_connect"))
    )
    (net (code "150") (name "unconnected-(PD2-NC#2-Pad14)") (class "Default")
      (node (ref "PD2") (pin "14") (pinfunction "NC#2_14") (pintype "no_connect"))
    )
    (net (code "151") (name "unconnected-(PD2-NC#3-Pad17)") (class "Default")
      (node (ref "PD2") (pin "17") (pinfunction "NC#3_17") (pintype "no_connect"))
    )
    (net (code "152") (name "unconnected-(PD2-NC#4-Pad22)") (class "Default")
      (node (ref "PD2") (pin "22") (pinfunction "NC#4_22") (pintype "no_connect"))
    )
    (net (code "153") (name "unconnected-(PD2-NC#5-Pad24)") (class "Default")
      (node (ref "PD2") (pin "24") (pinfunction "NC#5_24") (pintype "no_connect"))
    )
    (net (code "154") (name "unconnected-(PD2-NC#6-Pad29)") (class "Default")
      (node (ref "PD2") (pin "29") (pinfunction "NC#6_29") (pintype "no_connect"))
    )
    (net (code "155") (name "unconnected-(PD3-CP-Pad11)") (class "Default")
      (node (ref "PD3") (pin "11") (pinfunction "CP_11") (pintype "output"))
    )
    (net (code "156") (name "unconnected-(PD3-NC#1-Pad2)") (class "Default")
      (node (ref "PD3") (pin "2") (pinfunction "NC#1_2") (pintype "no_connect"))
    )
    (net (code "157") (name "unconnected-(PD3-NC#2-Pad14)") (class "Default")
      (node (ref "PD3") (pin "14") (pinfunction "NC#2_14") (pintype "no_connect"))
    )
    (net (code "158") (name "unconnected-(PD3-NC#3-Pad17)") (class "Default")
      (node (ref "PD3") (pin "17") (pinfunction "NC#3_17") (pintype "no_connect"))
    )
    (net (code "159") (name "unconnected-(PD3-NC#4-Pad22)") (class "Default")
      (node (ref "PD3") (pin "22") (pinfunction "NC#4_22") (pintype "no_connect"))
    )
    (net (code "160") (name "unconnected-(PD3-NC#5-Pad24)") (class "Default")
      (node (ref "PD3") (pin "24") (pinfunction "NC#5_24") (pintype "no_connect"))
    )
    (net (code "161") (name "unconnected-(PD3-NC#6-Pad29)") (class "Default")
      (node (ref "PD3") (pin "29") (pinfunction "NC#6_29") (pintype "no_connect"))
    )
    (net (code "162") (name "unconnected-(PD4-CP-Pad11)") (class "Default")
      (node (ref "PD4") (pin "11") (pinfunction "CP_11") (pintype "output"))
    )
    (net (code "163") (name "unconnected-(PD4-NC#1-Pad2)") (class "Default")
      (node (ref "PD4") (pin "2") (pinfunction "NC#1_2") (pintype "no_connect"))
    )
    (net (code "164") (name "unconnected-(PD4-NC#2-Pad14)") (class "Default")
      (node (ref "PD4") (pin "14") (pinfunction "NC#2_14") (pintype "no_connect"))
    )
    (net (code "165") (name "unconnected-(PD4-NC#3-Pad17)") (class "Default")
      (node (ref "PD4") (pin "17") (pinfunction "NC#3_17") (pintype "no_connect"))
    )
    (net (code "166") (name "unconnected-(PD4-NC#4-Pad22)") (class "Default")
      (node (ref "PD4") (pin "22") (pinfunction "NC#4_22") (pintype "no_connect"))
    )
    (net (code "167") (name "unconnected-(PD4-NC#5-Pad24)") (class "Default")
      (node (ref "PD4") (pin "24") (pinfunction "NC#5_24") (pintype "no_connect"))
    )
    (net (code "168") (name "unconnected-(PD4-NC#6-Pad29)") (class "Default")
      (node (ref "PD4") (pin "29") (pinfunction "NC#6_29") (pintype "no_connect"))
    )
    (net (code "169") (name "unconnected-(U1-PA_10-Pad69)") (class "Default")
      (node (ref "U1") (pin "69") (pinfunction "PA_10_69") (pintype "bidirectional"))
    )
  )
)
